# XMICRO-CF_V1_0.net
KiCad netlist of a schematic drawn in EAGLE
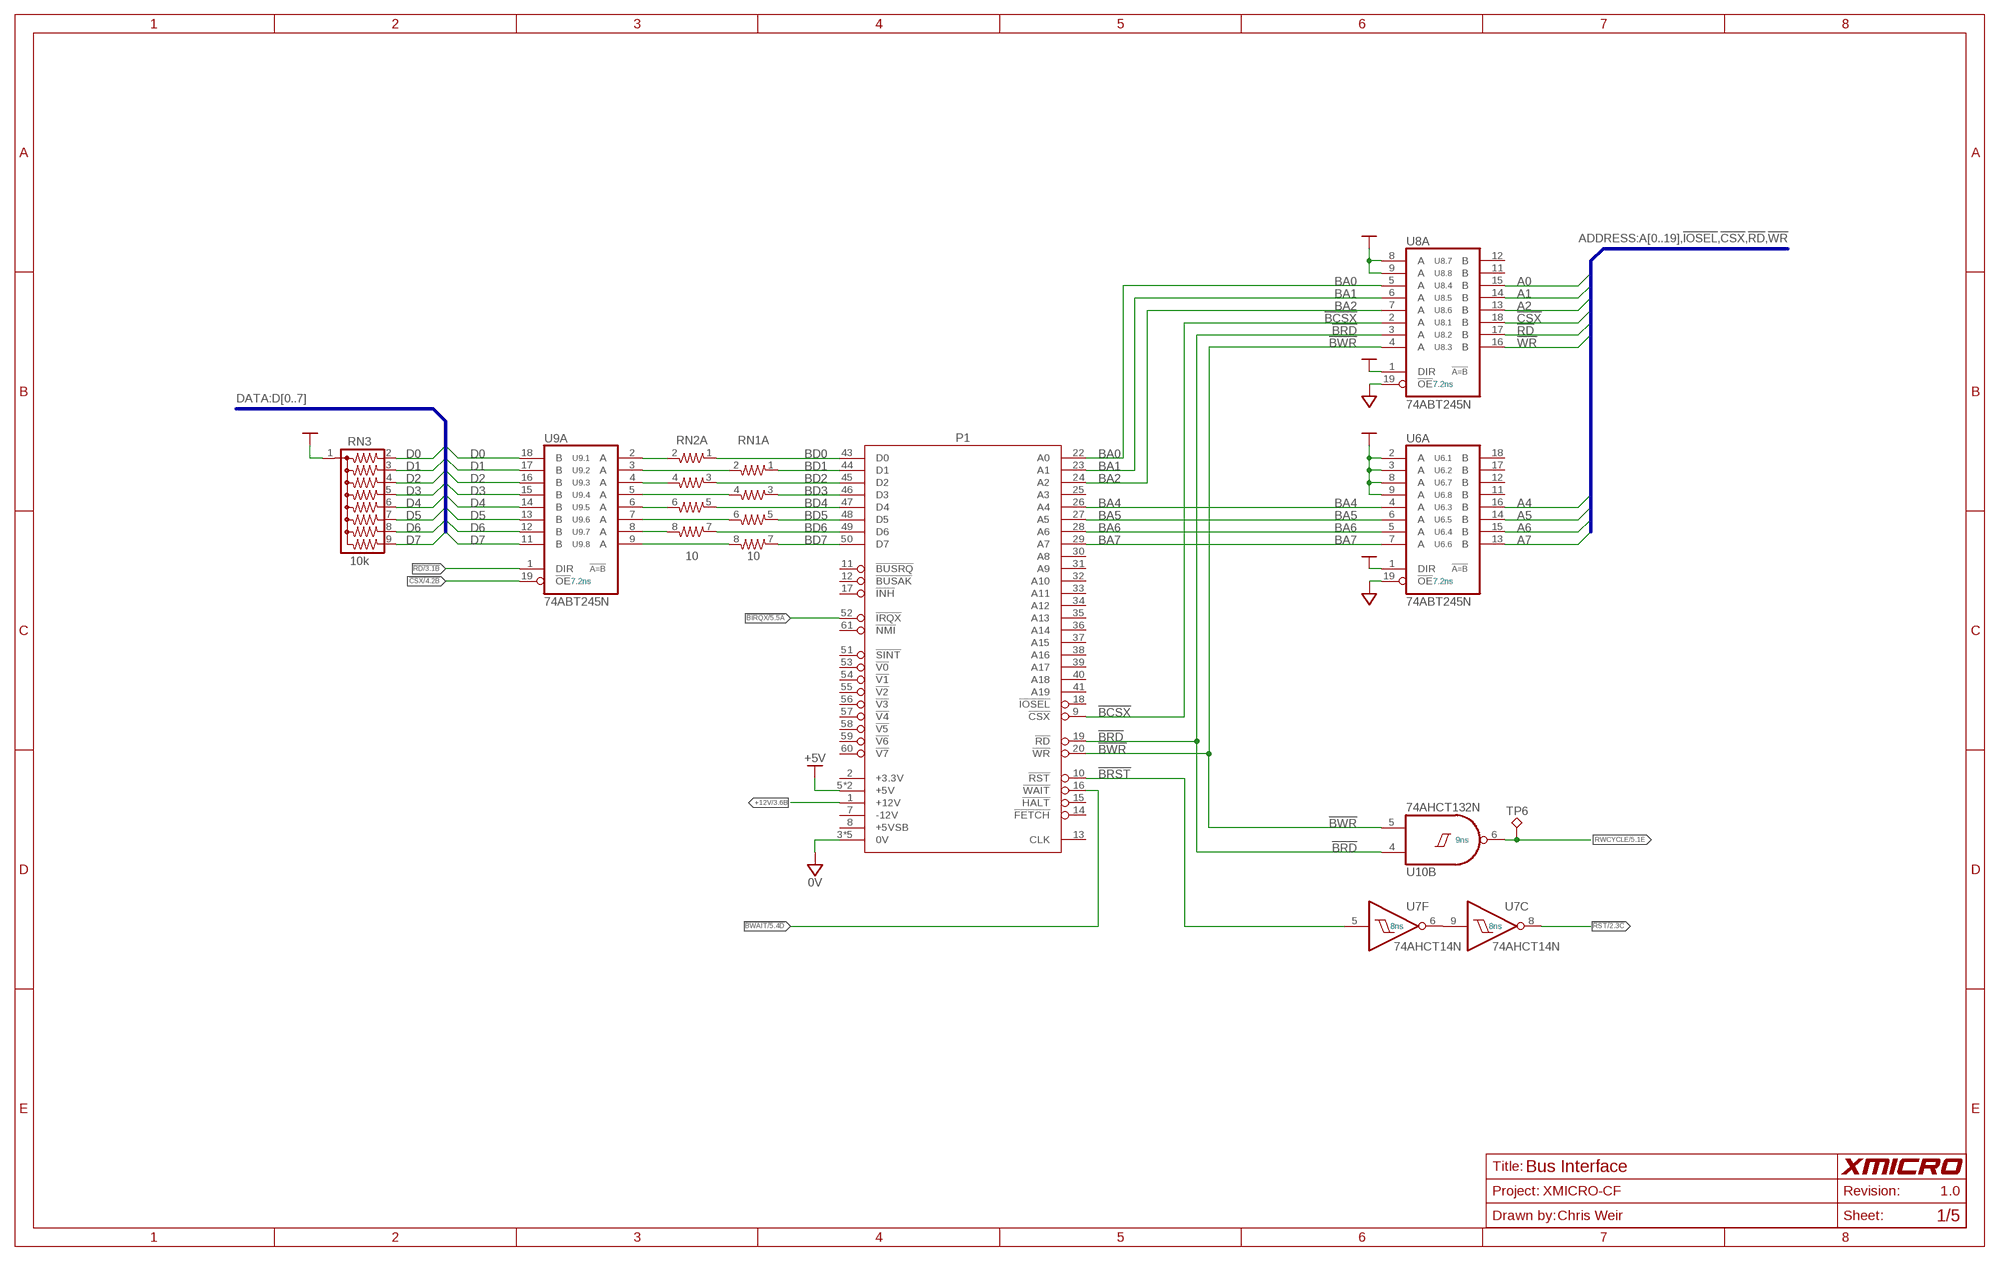
[diagram p0: schematic, sheet 1]
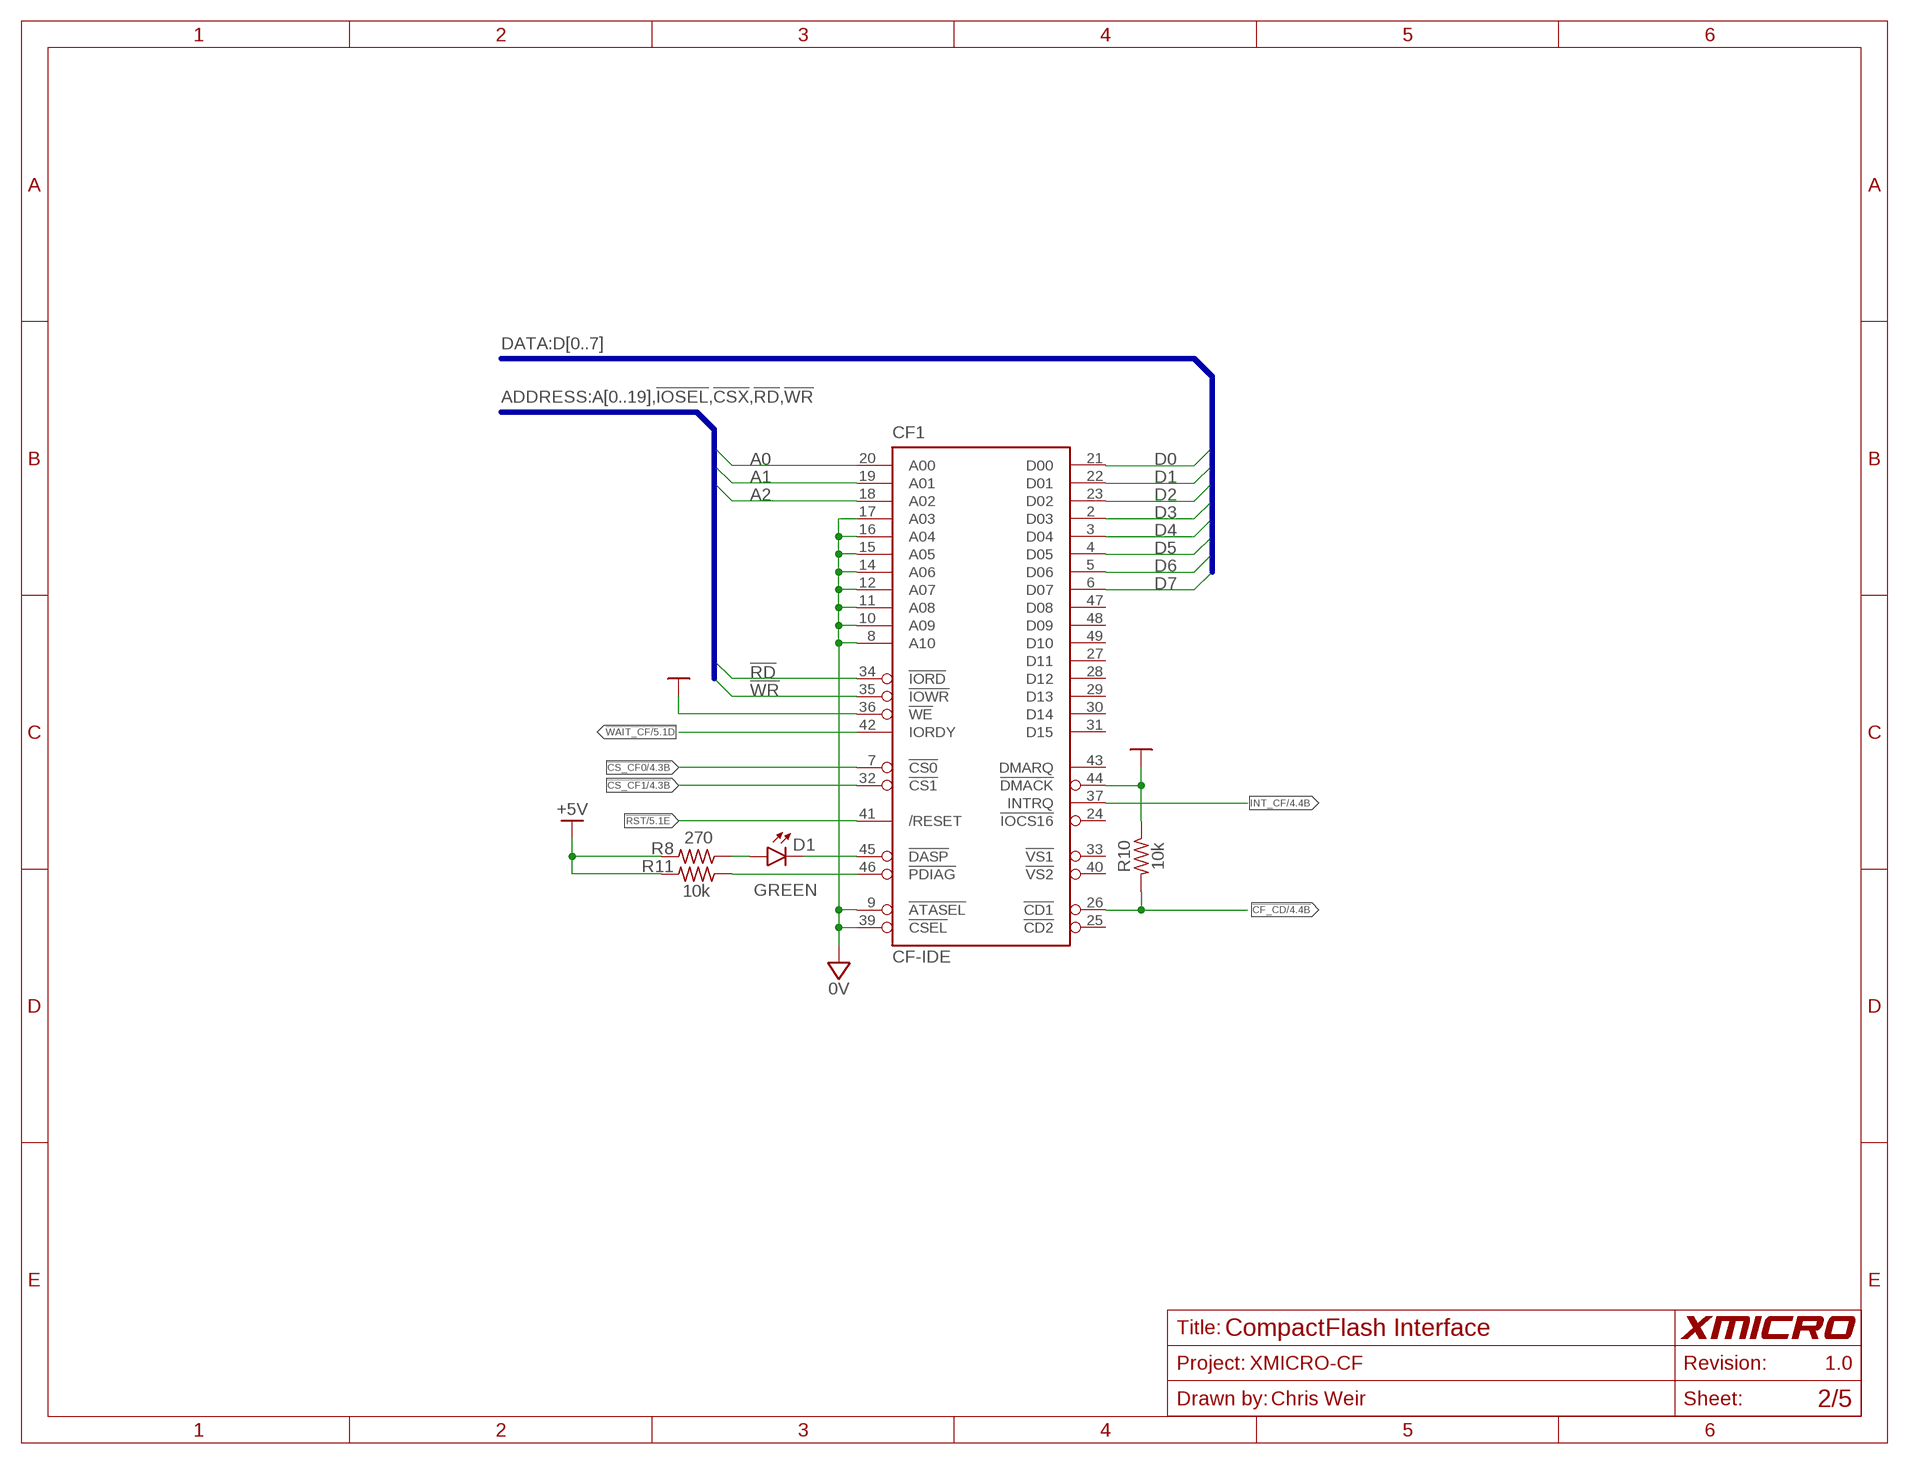
[diagram p1: schematic, sheet 2]
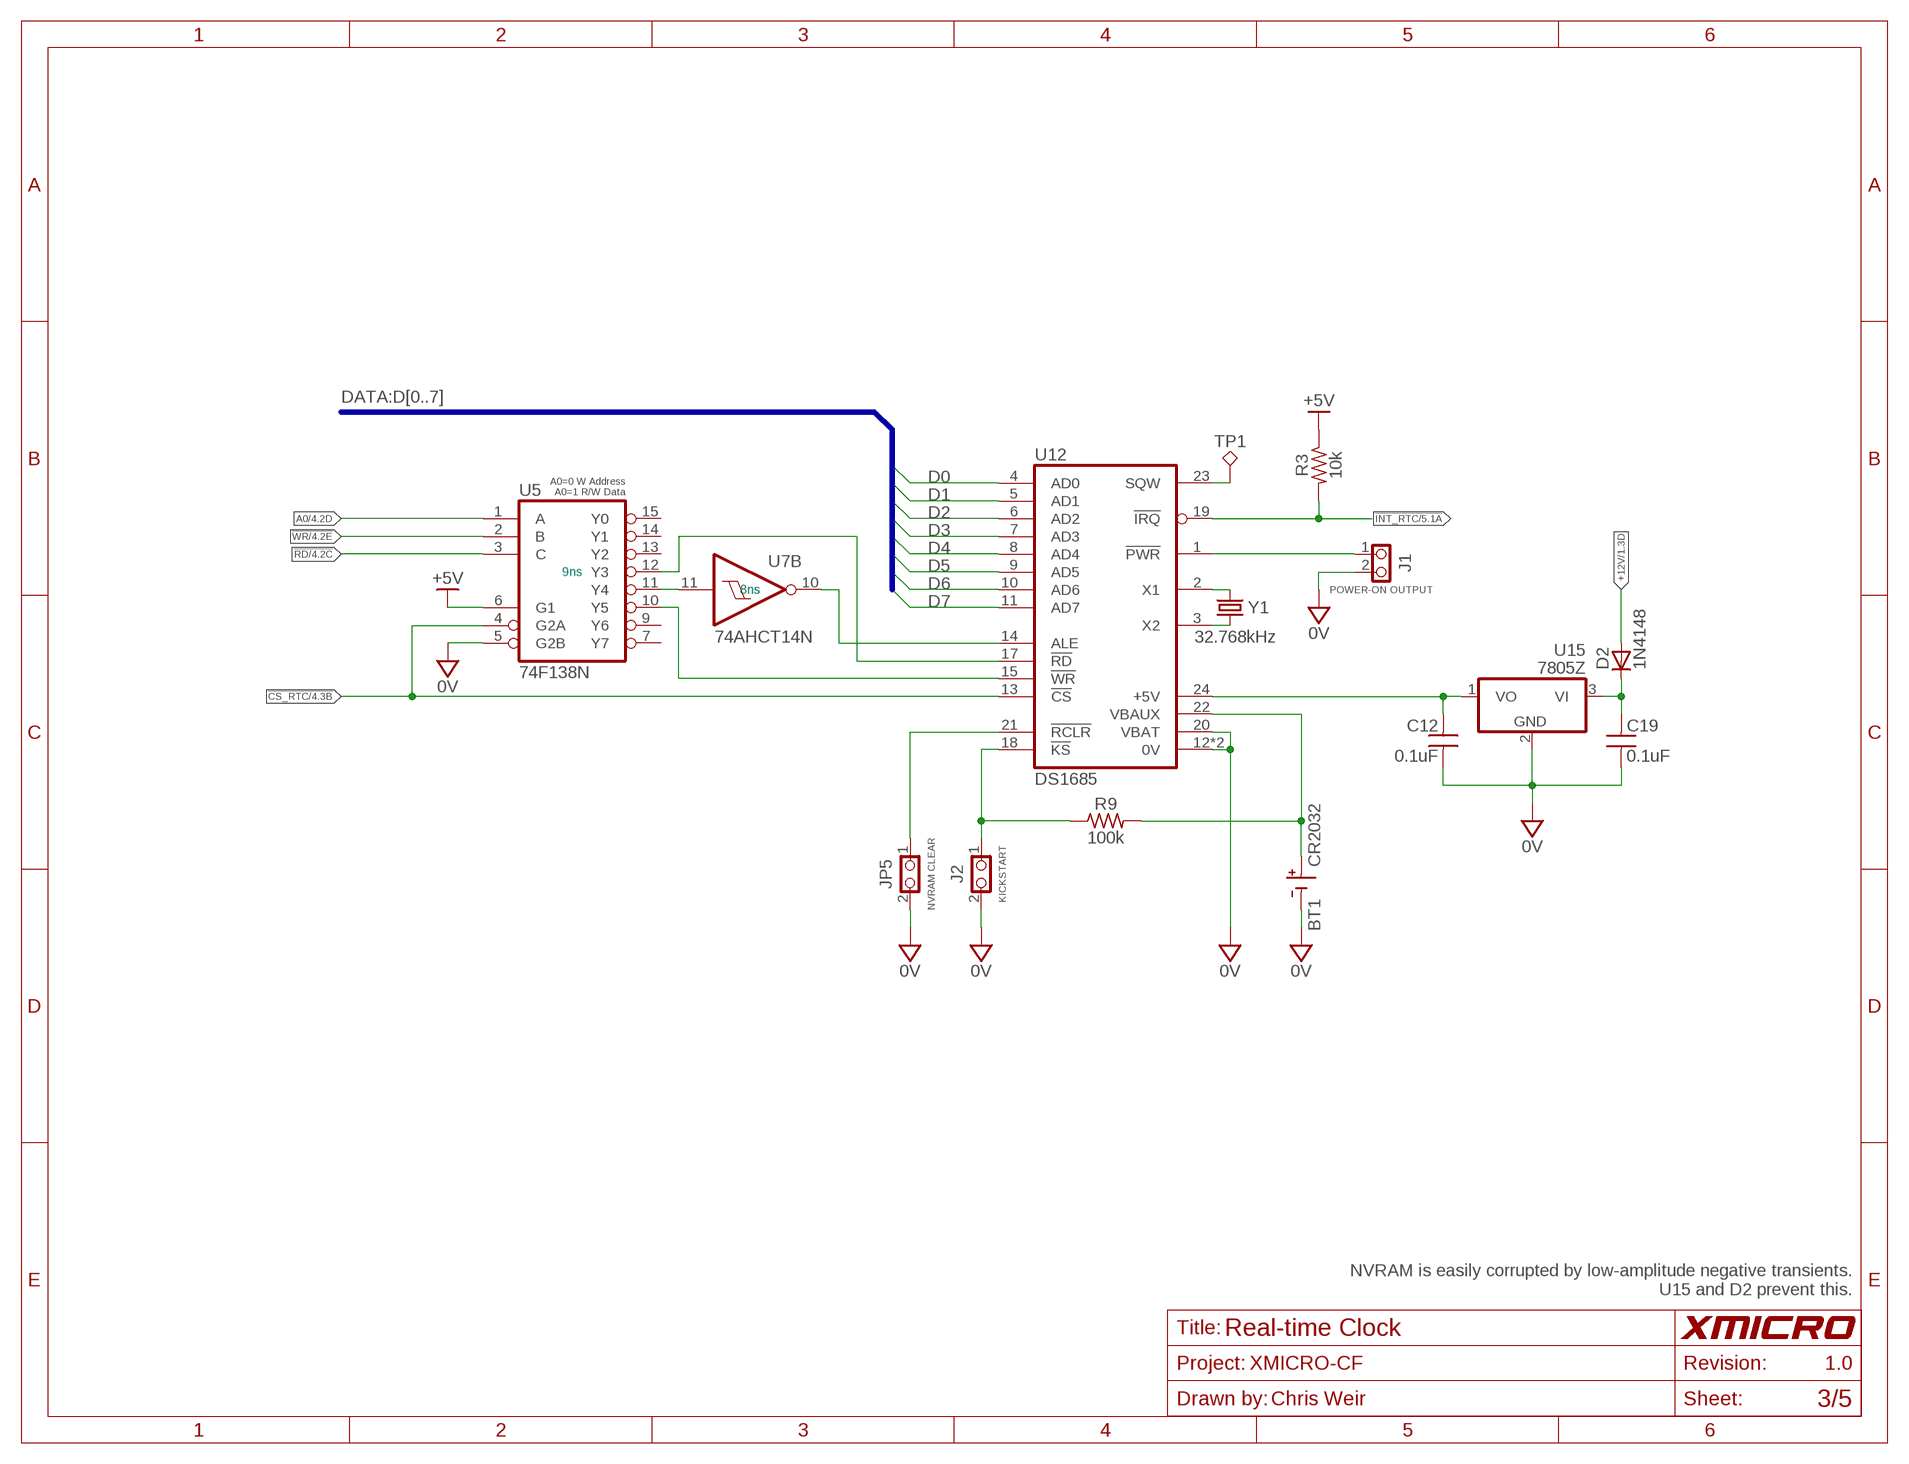
[diagram p2: schematic, sheet 3]
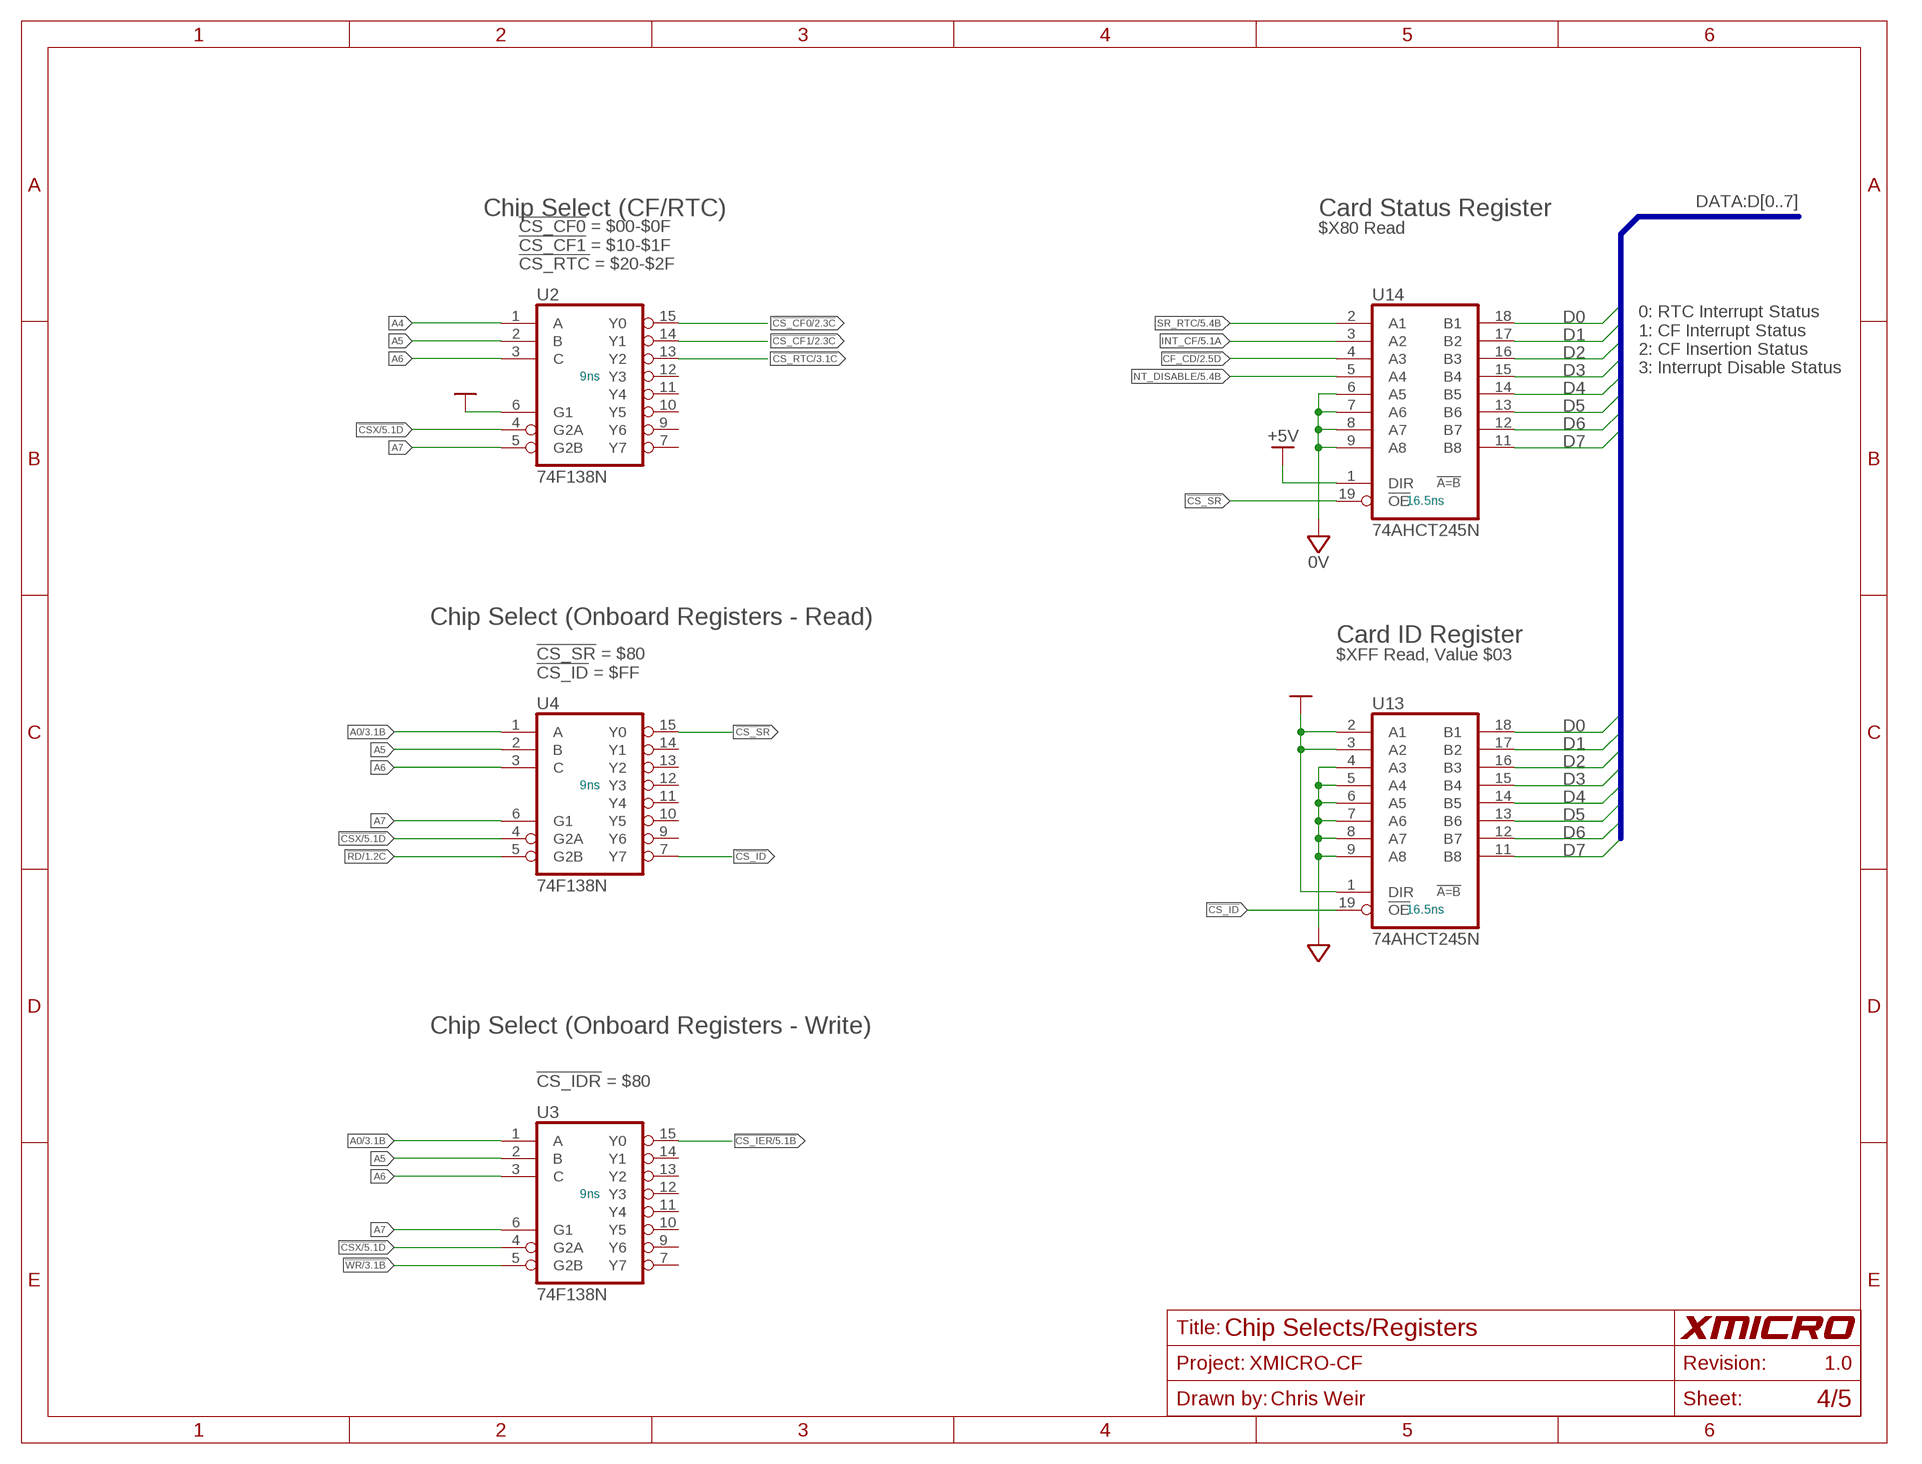
[diagram p3: schematic, sheet 4]
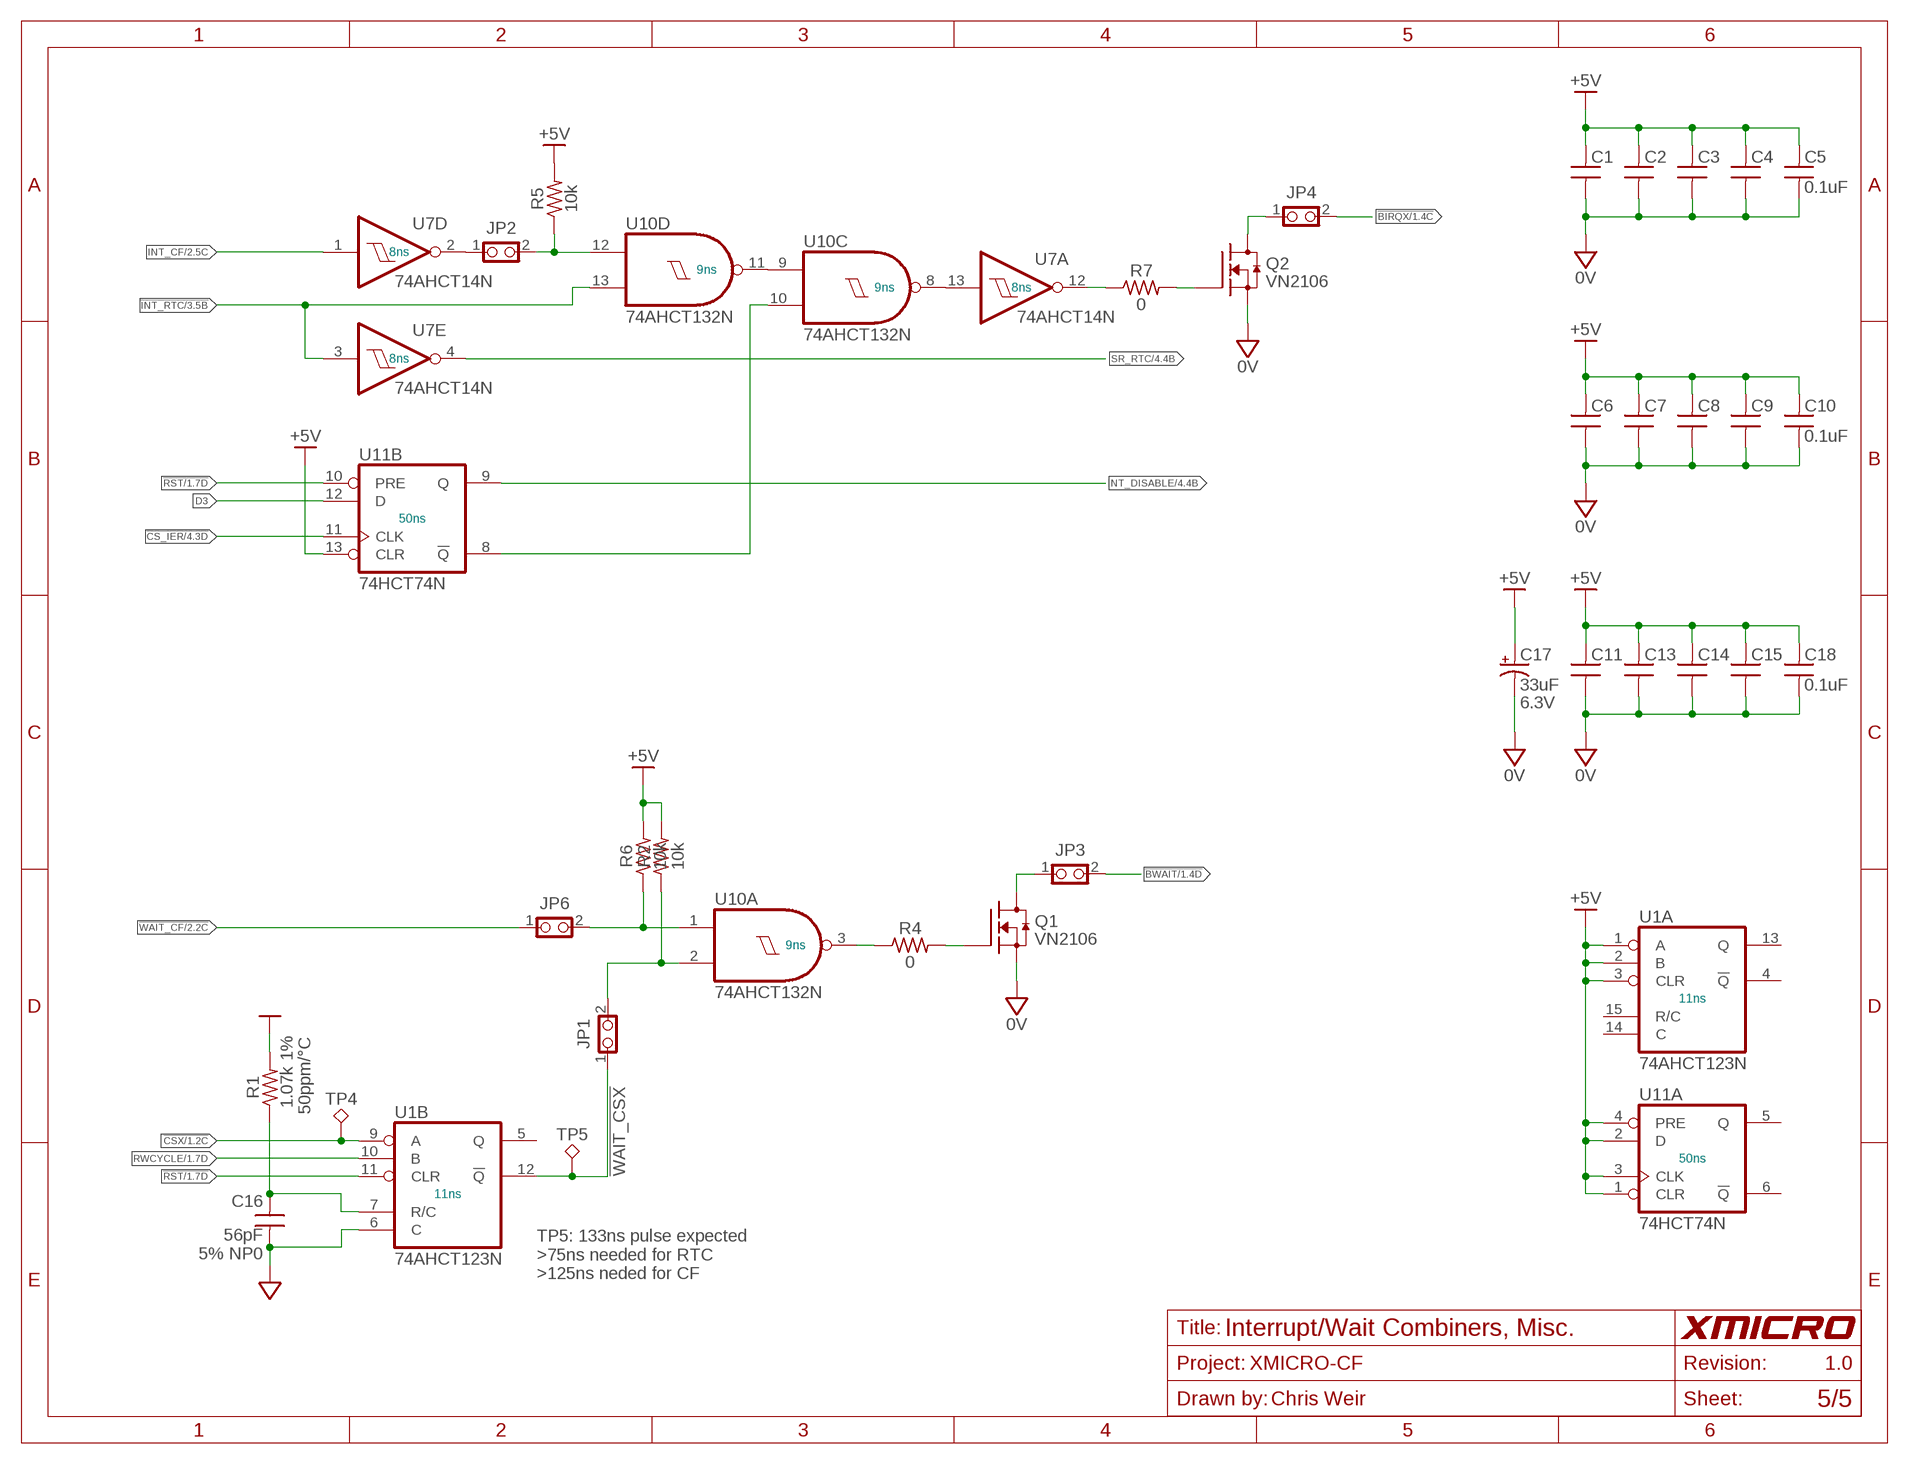
[diagram p4: schematic, sheet 5]

(export (version "E")
  (design (tool "Eeschema 10.0.6"))
  (components
    (comp (ref "C1")
      (value "0.1uF")
      (footprint "eagle-import:C025-024X044")
      (libsource (lib "eagle-import") (part "C-US025-024X044"))
    )
    (comp (ref "C2")
      (value "0.1uF")
      (footprint "eagle-import:C025-024X044")
      (libsource (lib "eagle-import") (part "C-US025-024X044"))
    )
    (comp (ref "C3")
      (value "0.1uF")
      (footprint "eagle-import:C025-024X044")
      (libsource (lib "eagle-import") (part "C-US025-024X044"))
    )
    (comp (ref "C4")
      (value "0.1uF")
      (footprint "eagle-import:C025-024X044")
      (libsource (lib "eagle-import") (part "C-US025-024X044"))
    )
    (comp (ref "C5")
      (value "0.1uF")
      (footprint "eagle-import:C025-024X044")
      (libsource (lib "eagle-import") (part "C-US025-024X044"))
    )
    (comp (ref "C6")
      (value "0.1uF")
      (footprint "eagle-import:C025-024X044")
      (libsource (lib "eagle-import") (part "C-US025-024X044"))
    )
    (comp (ref "C7")
      (value "0.1uF")
      (footprint "eagle-import:C025-024X044")
      (libsource (lib "eagle-import") (part "C-US025-024X044"))
    )
    (comp (ref "C8")
      (value "0.1uF")
      (footprint "eagle-import:C025-024X044")
      (libsource (lib "eagle-import") (part "C-US025-024X044"))
    )
    (comp (ref "C9")
      (value "0.1uF")
      (footprint "eagle-import:C025-024X044")
      (libsource (lib "eagle-import") (part "C-US025-024X044"))
    )
    (comp (ref "C10")
      (value "0.1uF")
      (footprint "eagle-import:C025-024X044")
      (libsource (lib "eagle-import") (part "C-US025-024X044"))
    )
    (comp (ref "C11")
      (value "0.1uF")
      (footprint "eagle-import:C025-024X044")
      (libsource (lib "eagle-import") (part "C-US025-024X044"))
    )
    (comp (ref "C13")
      (value "0.1uF")
      (footprint "eagle-import:C025-024X044")
      (libsource (lib "eagle-import") (part "C-US025-024X044"))
    )
    (comp (ref "C14")
      (value "0.1uF")
      (footprint "eagle-import:C025-024X044")
      (libsource (lib "eagle-import") (part "C-US025-024X044"))
    )
    (comp (ref "C15")
      (value "0.1uF")
      (footprint "eagle-import:C025-024X044")
      (libsource (lib "eagle-import") (part "C-US025-024X044"))
    )
    (comp (ref "C16")
      (value "56pF")
      (footprint "eagle-import:C025-024X044")
      (fields (field (name "TC") "NP0") (field (name "TOLERANCE") "5%"))
      (libsource (lib "eagle-import") (part "C-US025-024X044"))
    )
    (comp (ref "C17")
      (value "33uF")
      (footprint "eagle-import:E2,5-6")
      (fields (field (name "VOLTAGE") "6.3V"))
      (libsource (lib "eagle-import") (part "CPOL-USE2.5-6"))
    )
    (comp (ref "C18")
      (value "0.1uF")
      (footprint "eagle-import:C025-024X044")
      (libsource (lib "eagle-import") (part "C-US025-024X044"))
    )
    (comp (ref "JP1")
      (value "1X2-THRU")
      (footprint "eagle-import:1X2")
      (libsource (lib "eagle-import") (part "1X2-THRU"))
    )
    (comp (ref "JP2")
      (value "1X2-THRU")
      (footprint "eagle-import:1X2")
      (libsource (lib "eagle-import") (part "1X2-THRU"))
    )
    (comp (ref "JP3")
      (value "1X2-THRU")
      (footprint "eagle-import:1X2")
      (libsource (lib "eagle-import") (part "1X2-THRU"))
    )
    (comp (ref "JP4")
      (value "1X2-THRU")
      (footprint "eagle-import:1X2")
      (libsource (lib "eagle-import") (part "1X2-THRU"))
    )
    (comp (ref "JP6")
      (value "1X2-THRU")
      (footprint "eagle-import:1X2")
      (libsource (lib "eagle-import") (part "1X2-THRU"))
    )
    (comp (ref "Q1")
      (value "VN2106")
      (footprint "eagle-import:TO92")
      (libsource (lib "eagle-import") (part "VN2106"))
    )
    (comp (ref "Q2")
      (value "VN2106")
      (footprint "eagle-import:TO92")
      (libsource (lib "eagle-import") (part "VN2106"))
    )
    (comp (ref "R1")
      (value "1.07k")
      (footprint "eagle-import:0207_10")
      (fields (field (name "TC") "50ppm/°C") (field (name "TOLERANCE") "1%"))
      (libsource (lib "eagle-import") (part "R-US_0207/10"))
    )
    (comp (ref "R2")
      (value "10k")
      (footprint "eagle-import:0207_10")
      (libsource (lib "eagle-import") (part "R-US_0207/10"))
    )
    (comp (ref "R4")
      (value "0")
      (footprint "eagle-import:0207_10")
      (libsource (lib "eagle-import") (part "R-US_0207/10"))
    )
    (comp (ref "R5")
      (value "10k")
      (footprint "eagle-import:0207_10")
      (libsource (lib "eagle-import") (part "R-US_0207/10"))
    )
    (comp (ref "R6")
      (value "10k")
      (footprint "eagle-import:0207_10")
      (libsource (lib "eagle-import") (part "R-US_0207/10"))
    )
    (comp (ref "R7")
      (value "0")
      (footprint "eagle-import:0207_12")
      (libsource (lib "eagle-import") (part "R-US_0207/12"))
    )
    (comp (ref "TP4")
      (value "TP-040")
      (footprint "eagle-import:TP-040")
      (libsource (lib "eagle-import") (part "TP-040"))
    )
    (comp (ref "TP5")
      (value "TP-040")
      (footprint "eagle-import:TP-040")
      (libsource (lib "eagle-import") (part "TP-040"))
    )
    (comp (ref "U1")
      (value "74AHCT123N")
      (footprint "eagle-import:DIL16")
      (fields (field (name "TPD") "11ns"))
      (libsource (lib "eagle-import") (part "74123NAHCT"))
    )
    (comp (ref "U7")
      (value "74AHCT14N")
      (footprint "eagle-import:DIL14")
      (fields (field (name "TPD") "8ns") (field (name "TPD_1") "8ns"))
      (libsource (lib "eagle-import") (part "7414NAHCT"))
    )
    (comp (ref "U10")
      (value "74AHCT132N")
      (footprint "eagle-import:DIL14")
      (libsource (lib "eagle-import") (part "74132NAHCT"))
    )
    (comp (ref "U11")
      (value "74HCT74N")
      (footprint "eagle-import:DIL14")
      (libsource (lib "eagle-import") (part "7474NHCT"))
    )
    (comp (ref "P1")
      (value "XMICRO-BUS-EDGE")
      (footprint "eagle-import:EDGE62M")
      (libsource (lib "eagle-import") (part "XMICRO-BUS-EDGE"))
    )
    (comp (ref "RN1")
      (value "10")
      (footprint "eagle-import:SIL8")
      (libsource (lib "eagle-import") (part "E4R"))
    )
    (comp (ref "RN2")
      (value "10")
      (footprint "eagle-import:SIL8")
      (libsource (lib "eagle-import") (part "E4R"))
    )
    (comp (ref "RN3")
      (value "10k")
      (footprint "eagle-import:SIL9")
      (libsource (lib "eagle-import") (part "G08R"))
    )
    (comp (ref "TP6")
      (value "TP-040")
      (footprint "eagle-import:TP-040")
      (libsource (lib "eagle-import") (part "TP-040"))
    )
    (comp (ref "U6")
      (value "74ABT245N")
      (footprint "eagle-import:DIL20")
      (fields (field (name "TPD") "7.2ns"))
      (libsource (lib "eagle-import") (part "74245-SNABT"))
    )
    (comp (ref "U8")
      (value "74ABT245N")
      (footprint "eagle-import:DIL20")
      (libsource (lib "eagle-import") (part "74245-SNABT"))
    )
    (comp (ref "U9")
      (value "74ABT245N")
      (footprint "eagle-import:DIL20")
      (fields (field (name "TPD") "7.2ns"))
      (libsource (lib "eagle-import") (part "74245-SNABT"))
    )
    (comp (ref "CF1")
      (value "CF-IDE")
      (footprint "eagle-import:CF-KYOCERA")
      (libsource (lib "eagle-import") (part "CF-IDE"))
    )
    (comp (ref "D1")
      (value "GREEN")
      (footprint "eagle-import:LED-3R")
      (libsource (lib "eagle-import") (part "LED3MM-R"))
    )
    (comp (ref "R8")
      (value "270")
      (footprint "eagle-import:0207_10")
      (libsource (lib "eagle-import") (part "R-US_0207/10"))
    )
    (comp (ref "R10")
      (value "10k")
      (footprint "eagle-import:0207_10")
      (libsource (lib "eagle-import") (part "R-US_0207/10"))
    )
    (comp (ref "R11")
      (value "10k")
      (footprint "eagle-import:0207_10")
      (libsource (lib "eagle-import") (part "R-US_0207/10"))
    )
    (comp (ref "U2")
      (value "74F138N")
      (footprint "eagle-import:DIL16")
      (libsource (lib "eagle-import") (part "74138NF"))
    )
    (comp (ref "U3")
      (value "74F138N")
      (footprint "eagle-import:DIL16")
      (libsource (lib "eagle-import") (part "74138NF"))
    )
    (comp (ref "U4")
      (value "74F138N")
      (footprint "eagle-import:DIL16")
      (libsource (lib "eagle-import") (part "74138NF"))
    )
    (comp (ref "U13")
      (value "74AHCT245N")
      (footprint "eagle-import:DIL20")
      (libsource (lib "eagle-import") (part "74245NAHCT"))
    )
    (comp (ref "U14")
      (value "74AHCT245N")
      (footprint "eagle-import:DIL20")
      (libsource (lib "eagle-import") (part "74245NAHCT"))
    )
    (comp (ref "BT1")
      (value "CR2032")
      (footprint "eagle-import:BU2032")
      (libsource (lib "eagle-import") (part "CR2032TH"))
    )
    (comp (ref "C12")
      (value "0.1uF")
      (footprint "eagle-import:C025-024X044")
      (libsource (lib "eagle-import") (part "C-US025-024X044"))
    )
    (comp (ref "C19")
      (value "0.1uF")
      (footprint "eagle-import:C025-024X044")
      (libsource (lib "eagle-import") (part "C-US025-024X044"))
    )
    (comp (ref "D2")
      (value "1N4148")
      (footprint "eagle-import:DO35-7")
      (libsource (lib "eagle-import") (part "1N4148DO35-7"))
    )
    (comp (ref "J1")
      (value "1X2")
      (footprint "eagle-import:1X2")
      (libsource (lib "eagle-import") (part "1X2"))
    )
    (comp (ref "J2")
      (value "1X2-THRU")
      (footprint "eagle-import:1X2")
      (libsource (lib "eagle-import") (part "1X2-THRU"))
    )
    (comp (ref "JP5")
      (value "1X2-THRU")
      (footprint "eagle-import:1X2")
      (libsource (lib "eagle-import") (part "1X2-THRU"))
    )
    (comp (ref "R3")
      (value "10k")
      (footprint "eagle-import:0207_10")
      (libsource (lib "eagle-import") (part "R-US_0207/10"))
    )
    (comp (ref "R9")
      (value "100k")
      (footprint "eagle-import:0207_10")
      (libsource (lib "eagle-import") (part "R-US_0207/10"))
    )
    (comp (ref "TP1")
      (value "TP-040")
      (footprint "eagle-import:TP-040")
      (libsource (lib "eagle-import") (part "TP-040"))
    )
    (comp (ref "U5")
      (value "74F138N")
      (footprint "eagle-import:DIL16")
      (libsource (lib "eagle-import") (part "74138NF"))
    )
    (comp (ref "U12")
      (value "DS1685")
      (footprint "eagle-import:DIL24")
      (libsource (lib "eagle-import") (part "DS1685"))
    )
    (comp (ref "U15")
      (value "7805Z")
      (footprint "eagle-import:TO92")
      (libsource (lib "eagle-import") (part "78Z05"))
    )
    (comp (ref "Y1")
      (value "32.768kHz")
      (footprint "eagle-import:CRYSTAL-3X8N")
      (libsource (lib "eagle-import") (part "CRYSTAL-3X8"))
    )
  )
  (nets
    (net (code "36") (name "+5V") (class "Default")
      (node (ref "C1") (pin "1") (pinfunction "1_1") (pintype "passive"))
      (node (ref "C10") (pin "1") (pinfunction "1_1") (pintype "passive"))
      (node (ref "C11") (pin "1") (pinfunction "1_1") (pintype "passive"))
      (node (ref "C13") (pin "1") (pinfunction "1_1") (pintype "passive"))
      (node (ref "C14") (pin "1") (pinfunction "1_1") (pintype "passive"))
      (node (ref "C15") (pin "1") (pinfunction "1_1") (pintype "passive"))
      (node (ref "C17") (pin "+") (pinfunction "+_+") (pintype "passive"))
      (node (ref "C18") (pin "1") (pinfunction "1_1") (pintype "passive"))
      (node (ref "C2") (pin "1") (pinfunction "1_1") (pintype "passive"))
      (node (ref "C3") (pin "1") (pinfunction "1_1") (pintype "passive"))
      (node (ref "C4") (pin "1") (pinfunction "1_1") (pintype "passive"))
      (node (ref "C5") (pin "1") (pinfunction "1_1") (pintype "passive"))
      (node (ref "C6") (pin "1") (pinfunction "1_1") (pintype "passive"))
      (node (ref "C7") (pin "1") (pinfunction "1_1") (pintype "passive"))
      (node (ref "C8") (pin "1") (pinfunction "1_1") (pintype "passive"))
      (node (ref "C9") (pin "1") (pinfunction "1_1") (pintype "passive"))
      (node (ref "CF1") (pin "36") (pinfunction "~{WE}_36") (pintype "input"))
      (node (ref "CF1") (pin "44") (pinfunction "~{DMACK}_44") (pintype "input"))
      (node (ref "P1") (pin "5") (pinfunction "+5V_5") (pintype "bidirectional"))
      (node (ref "P1") (pin "6") (pinfunction "+5V_6") (pintype "bidirectional"))
      (node (ref "R1") (pin "2") (pinfunction "2_2") (pintype "passive"))
      (node (ref "R10") (pin "1") (pinfunction "1_1") (pintype "passive"))
      (node (ref "R11") (pin "2") (pinfunction "2_2") (pintype "passive"))
      (node (ref "R2") (pin "2") (pinfunction "2_2") (pintype "passive"))
      (node (ref "R3") (pin "1") (pinfunction "1_1") (pintype "passive"))
      (node (ref "R5") (pin "2") (pinfunction "2_2") (pintype "passive"))
      (node (ref "R6") (pin "2") (pinfunction "2_2") (pintype "passive"))
      (node (ref "R8") (pin "2") (pinfunction "2_2") (pintype "passive"))
      (node (ref "RN3") (pin "1") (pinfunction "1_1") (pintype "passive"))
      (node (ref "U1") (pin "1") (pinfunction "A_1") (pintype "input"))
      (node (ref "U1") (pin "2") (pinfunction "B_2") (pintype "input"))
      (node (ref "U1") (pin "3") (pinfunction "CLR_3") (pintype "input"))
      (node (ref "U11") (pin "1") (pinfunction "CLR_1") (pintype "input"))
      (node (ref "U11") (pin "13") (pinfunction "CLR_13") (pintype "input"))
      (node (ref "U11") (pin "2") (pinfunction "D_2") (pintype "input"))
      (node (ref "U11") (pin "3") (pinfunction "CLK_3") (pintype "input"))
      (node (ref "U11") (pin "4") (pinfunction "PRE_4") (pintype "input"))
      (node (ref "U13") (pin "1") (pinfunction "DIR_1") (pintype "input"))
      (node (ref "U13") (pin "2") (pinfunction "A1_2") (pintype "bidirectional"))
      (node (ref "U13") (pin "3") (pinfunction "A2_3") (pintype "bidirectional"))
      (node (ref "U14") (pin "1") (pinfunction "DIR_1") (pintype "input"))
      (node (ref "U2") (pin "6") (pinfunction "G1_6") (pintype "input"))
      (node (ref "U5") (pin "6") (pinfunction "G1_6") (pintype "input"))
      (node (ref "U6") (pin "1") (pinfunction "DIR_1") (pintype "input"))
      (node (ref "U6") (pin "2") (pinfunction "A_2") (pintype "bidirectional"))
      (node (ref "U6") (pin "3") (pinfunction "A_3") (pintype "bidirectional"))
      (node (ref "U6") (pin "8") (pinfunction "A_8") (pintype "bidirectional"))
      (node (ref "U6") (pin "9") (pinfunction "A_9") (pintype "bidirectional"))
      (node (ref "U8") (pin "1") (pinfunction "DIR_1") (pintype "input"))
      (node (ref "U8") (pin "8") (pinfunction "A_8") (pintype "bidirectional"))
      (node (ref "U8") (pin "9") (pinfunction "A_9") (pintype "bidirectional"))
    )
    (net (code "37") (name "+12V") (class "Default")
      (node (ref "D2") (pin "A") (pinfunction "A_A") (pintype "passive"))
      (node (ref "P1") (pin "1") (pinfunction "+12V_1") (pintype "bidirectional"))
    )
    (net (code "44") (name "0V") (class "Default")
      (node (ref "BT1") (pin "N") (pinfunction "-_N") (pintype "passive"))
      (node (ref "C1") (pin "2") (pinfunction "2_2") (pintype "passive"))
      (node (ref "C10") (pin "2") (pinfunction "2_2") (pintype "passive"))
      (node (ref "C11") (pin "2") (pinfunction "2_2") (pintype "passive"))
      (node (ref "C12") (pin "2") (pinfunction "2_2") (pintype "passive"))
      (node (ref "C13") (pin "2") (pinfunction "2_2") (pintype "passive"))
      (node (ref "C14") (pin "2") (pinfunction "2_2") (pintype "passive"))
      (node (ref "C15") (pin "2") (pinfunction "2_2") (pintype "passive"))
      (node (ref "C16") (pin "2") (pinfunction "2_2") (pintype "passive"))
      (node (ref "C17") (pin "-") (pinfunction "-_-") (pintype "passive"))
      (node (ref "C18") (pin "2") (pinfunction "2_2") (pintype "passive"))
      (node (ref "C19") (pin "2") (pinfunction "2_2") (pintype "passive"))
      (node (ref "C2") (pin "2") (pinfunction "2_2") (pintype "passive"))
      (node (ref "C3") (pin "2") (pinfunction "2_2") (pintype "passive"))
      (node (ref "C4") (pin "2") (pinfunction "2_2") (pintype "passive"))
      (node (ref "C5") (pin "2") (pinfunction "2_2") (pintype "passive"))
      (node (ref "C6") (pin "2") (pinfunction "2_2") (pintype "passive"))
      (node (ref "C7") (pin "2") (pinfunction "2_2") (pintype "passive"))
      (node (ref "C8") (pin "2") (pinfunction "2_2") (pintype "passive"))
      (node (ref "C9") (pin "2") (pinfunction "2_2") (pintype "passive"))
      (node (ref "CF1") (pin "10") (pinfunction "A09_10") (pintype "input"))
      (node (ref "CF1") (pin "11") (pinfunction "A08_11") (pintype "input"))
      (node (ref "CF1") (pin "12") (pinfunction "A07_12") (pintype "input"))
      (node (ref "CF1") (pin "14") (pinfunction "A06_14") (pintype "input"))
      (node (ref "CF1") (pin "15") (pinfunction "A05_15") (pintype "input"))
      (node (ref "CF1") (pin "16") (pinfunction "A04_16") (pintype "input"))
      (node (ref "CF1") (pin "17") (pinfunction "A03_17") (pintype "input"))
      (node (ref "CF1") (pin "39") (pinfunction "~{CSEL}_39") (pintype "input"))
      (node (ref "CF1") (pin "8") (pinfunction "A10_8") (pintype "input"))
      (node (ref "CF1") (pin "9") (pinfunction "~{ATASEL}_9") (pintype "input"))
      (node (ref "J1") (pin "2") (pinfunction "2_2") (pintype "passive"))
      (node (ref "J2") (pin "2") (pinfunction "2_2") (pintype "passive"))
      (node (ref "JP5") (pin "2") (pinfunction "2_2") (pintype "passive"))
      (node (ref "P1") (pin "21") (pinfunction "0V_21") (pintype "bidirectional"))
      (node (ref "P1") (pin "3") (pinfunction "0V_3") (pintype "bidirectional"))
      (node (ref "P1") (pin "4") (pinfunction "0V_4") (pintype "bidirectional"))
      (node (ref "P1") (pin "42") (pinfunction "0V_42") (pintype "bidirectional"))
      (node (ref "P1") (pin "62") (pinfunction "0V_62") (pintype "bidirectional"))
      (node (ref "Q1") (pin "1") (pinfunction "S_1") (pintype "passive"))
      (node (ref "Q2") (pin "1") (pinfunction "S_1") (pintype "passive"))
      (node (ref "U1") (pin "6") (pinfunction "C_6") (pintype "input"))
      (node (ref "U12") (pin "12") (pinfunction "0V_12") (pintype "input"))
      (node (ref "U12") (pin "16") (pinfunction "0V_16") (pintype "input"))
      (node (ref "U12") (pin "20") (pinfunction "VBAT_20") (pintype "input"))
      (node (ref "U13") (pin "4") (pinfunction "A3_4") (pintype "bidirectional"))
      (node (ref "U13") (pin "5") (pinfunction "A4_5") (pintype "bidirectional"))
      (node (ref "U13") (pin "6") (pinfunction "A5_6") (pintype "bidirectional"))
      (node (ref "U13") (pin "7") (pinfunction "A6_7") (pintype "bidirectional"))
      (node (ref "U13") (pin "8") (pinfunction "A7_8") (pintype "bidirectional"))
      (node (ref "U13") (pin "9") (pinfunction "A8_9") (pintype "bidirectional"))
      (node (ref "U14") (pin "6") (pinfunction "A5_6") (pintype "bidirectional"))
      (node (ref "U14") (pin "7") (pinfunction "A6_7") (pintype "bidirectional"))
      (node (ref "U14") (pin "8") (pinfunction "A7_8") (pintype "bidirectional"))
      (node (ref "U14") (pin "9") (pinfunction "A8_9") (pintype "bidirectional"))
      (node (ref "U15") (pin "2") (pinfunction "0V_2") (pintype "passive"))
      (node (ref "U5") (pin "5") (pinfunction "G2B_5") (pintype "input"))
      (node (ref "U6") (pin "19") (pinfunction "~{OE}_19") (pintype "input"))
      (node (ref "U8") (pin "19") (pinfunction "~{OE}_19") (pintype "input"))
    )
    (net (code "45") (name "A0") (class "Default")
      (node (ref "CF1") (pin "20") (pinfunction "A00_20") (pintype "input"))
      (node (ref "U3") (pin "1") (pinfunction "A_1") (pintype "input"))
      (node (ref "U4") (pin "1") (pinfunction "A_1") (pintype "input"))
      (node (ref "U5") (pin "1") (pinfunction "A_1") (pintype "input"))
      (node (ref "U8") (pin "15") (pinfunction "B_15") (pintype "bidirectional"))
    )
    (net (code "46") (name "A1") (class "Default")
      (node (ref "CF1") (pin "19") (pinfunction "A01_19") (pintype "input"))
      (node (ref "U8") (pin "14") (pinfunction "B_14") (pintype "bidirectional"))
    )
    (net (code "47") (name "A2") (class "Default")
      (node (ref "CF1") (pin "18") (pinfunction "A02_18") (pintype "input"))
      (node (ref "U8") (pin "13") (pinfunction "B_13") (pintype "bidirectional"))
    )
    (net (code "48") (name "A4") (class "Default")
      (node (ref "U2") (pin "1") (pinfunction "A_1") (pintype "input"))
      (node (ref "U6") (pin "16") (pinfunction "B_16") (pintype "bidirectional"))
    )
    (net (code "49") (name "A5") (class "Default")
      (node (ref "U2") (pin "2") (pinfunction "B_2") (pintype "input"))
      (node (ref "U3") (pin "2") (pinfunction "B_2") (pintype "input"))
      (node (ref "U4") (pin "2") (pinfunction "B_2") (pintype "input"))
      (node (ref "U6") (pin "14") (pinfunction "B_14") (pintype "bidirectional"))
    )
    (net (code "50") (name "A6") (class "Default")
      (node (ref "U2") (pin "3") (pinfunction "C_3") (pintype "input"))
      (node (ref "U3") (pin "3") (pinfunction "C_3") (pintype "input"))
      (node (ref "U4") (pin "3") (pinfunction "C_3") (pintype "input"))
      (node (ref "U6") (pin "15") (pinfunction "B_15") (pintype "bidirectional"))
    )
    (net (code "51") (name "A7") (class "Default")
      (node (ref "U2") (pin "5") (pinfunction "G2B_5") (pintype "input"))
      (node (ref "U3") (pin "6") (pinfunction "G1_6") (pintype "input"))
      (node (ref "U4") (pin "6") (pinfunction "G1_6") (pintype "input"))
      (node (ref "U6") (pin "13") (pinfunction "B_13") (pintype "bidirectional"))
    )
    (net (code "52") (name "BA0") (class "Default")
      (node (ref "P1") (pin "22") (pinfunction "A0_22") (pintype "bidirectional"))
      (node (ref "U8") (pin "5") (pinfunction "A_5") (pintype "bidirectional"))
    )
    (net (code "53") (name "BA1") (class "Default")
      (node (ref "P1") (pin "23") (pinfunction "A1_23") (pintype "bidirectional"))
      (node (ref "U8") (pin "6") (pinfunction "A_6") (pintype "bidirectional"))
    )
    (net (code "54") (name "BA2") (class "Default")
      (node (ref "P1") (pin "24") (pinfunction "A2_24") (pintype "bidirectional"))
      (node (ref "U8") (pin "7") (pinfunction "A_7") (pintype "bidirectional"))
    )
    (net (code "55") (name "BA4") (class "Default")
      (node (ref "P1") (pin "26") (pinfunction "A4_26") (pintype "bidirectional"))
      (node (ref "U6") (pin "4") (pinfunction "A_4") (pintype "bidirectional"))
    )
    (net (code "56") (name "BA5") (class "Default")
      (node (ref "P1") (pin "27") (pinfunction "A5_27") (pintype "bidirectional"))
      (node (ref "U6") (pin "6") (pinfunction "A_6") (pintype "bidirectional"))
    )
    (net (code "57") (name "BA6") (class "Default")
      (node (ref "P1") (pin "28") (pinfunction "A6_28") (pintype "bidirectional"))
      (node (ref "U6") (pin "5") (pinfunction "A_5") (pintype "bidirectional"))
    )
    (net (code "58") (name "BA7") (class "Default")
      (node (ref "P1") (pin "29") (pinfunction "A7_29") (pintype "bidirectional"))
      (node (ref "U6") (pin "7") (pinfunction "A_7") (pintype "bidirectional"))
    )
    (net (code "59") (name "BD0") (class "Default")
      (node (ref "P1") (pin "43") (pinfunction "D0_43") (pintype "bidirectional"))
      (node (ref "RN2") (pin "1") (pinfunction "1_1") (pintype "passive"))
    )
    (net (code "60") (name "BD1") (class "Default")
      (node (ref "P1") (pin "44") (pinfunction "D1_44") (pintype "bidirectional"))
      (node (ref "RN1") (pin "1") (pinfunction "1_1") (pintype "passive"))
    )
    (net (code "61") (name "BD2") (class "Default")
      (node (ref "P1") (pin "45") (pinfunction "D2_45") (pintype "bidirectional"))
      (node (ref "RN2") (pin "3") (pinfunction "1_3") (pintype "passive"))
    )
    (net (code "62") (name "BD3") (class "Default")
      (node (ref "P1") (pin "46") (pinfunction "D3_46") (pintype "bidirectional"))
      (node (ref "RN1") (pin "3") (pinfunction "1_3") (pintype "passive"))
    )
    (net (code "63") (name "BD4") (class "Default")
      (node (ref "P1") (pin "47") (pinfunction "D4_47") (pintype "bidirectional"))
      (node (ref "RN2") (pin "5") (pinfunction "1_5") (pintype "passive"))
    )
    (net (code "64") (name "BD5") (class "Default")
      (node (ref "P1") (pin "48") (pinfunction "D5_48") (pintype "bidirectional"))
      (node (ref "RN1") (pin "5") (pinfunction "1_5") (pintype "passive"))
    )
    (net (code "65") (name "BD6") (class "Default")
      (node (ref "P1") (pin "49") (pinfunction "D6_49") (pintype "bidirectional"))
      (node (ref "RN2") (pin "7") (pinfunction "1_7") (pintype "passive"))
    )
    (net (code "66") (name "BD7") (class "Default")
      (node (ref "P1") (pin "50") (pinfunction "D7_50") (pintype "bidirectional"))
      (node (ref "RN1") (pin "7") (pinfunction "1_7") (pintype "passive"))
    )
    (net (code "67") (name "D0") (class "Default")
      (node (ref "CF1") (pin "21") (pinfunction "D00_21") (pintype "tri_state"))
      (node (ref "RN3") (pin "2") (pinfunction "2_2") (pintype "passive"))
      (node (ref "U12") (pin "4") (pinfunction "AD0_4") (pintype "tri_state"))
      (node (ref "U13") (pin "18") (pinfunction "B1_18") (pintype "bidirectional"))
      (node (ref "U14") (pin "18") (pinfunction "B1_18") (pintype "bidirectional"))
      (node (ref "U9") (pin "18") (pinfunction "B_18") (pintype "bidirectional"))
    )
    (net (code "68") (name "D1") (class "Default")
      (node (ref "CF1") (pin "22") (pinfunction "D01_22") (pintype "tri_state"))
      (node (ref "RN3") (pin "3") (pinfunction "3_3") (pintype "passive"))
      (node (ref "U12") (pin "5") (pinfunction "AD1_5") (pintype "tri_state"))
      (node (ref "U13") (pin "17") (pinfunction "B2_17") (pintype "bidirectional"))
      (node (ref "U14") (pin "17") (pinfunction "B2_17") (pintype "bidirectional"))
      (node (ref "U9") (pin "17") (pinfunction "B_17") (pintype "bidirectional"))
    )
    (net (code "69") (name "D2") (class "Default")
      (node (ref "CF1") (pin "23") (pinfunction "D02_23") (pintype "tri_state"))
      (node (ref "RN3") (pin "4") (pinfunction "4_4") (pintype "passive"))
      (node (ref "U12") (pin "6") (pinfunction "AD2_6") (pintype "tri_state"))
      (node (ref "U13") (pin "16") (pinfunction "B3_16") (pintype "bidirectional"))
      (node (ref "U14") (pin "16") (pinfunction "B3_16") (pintype "bidirectional"))
      (node (ref "U9") (pin "16") (pinfunction "B_16") (pintype "bidirectional"))
    )
    (net (code "70") (name "D3") (class "Default")
      (node (ref "CF1") (pin "2") (pinfunction "D03_2") (pintype "tri_state"))
      (node (ref "RN3") (pin "5") (pinfunction "5_5") (pintype "passive"))
      (node (ref "U11") (pin "12") (pinfunction "D_12") (pintype "input"))
      (node (ref "U12") (pin "7") (pinfunction "AD3_7") (pintype "tri_state"))
      (node (ref "U13") (pin "15") (pinfunction "B4_15") (pintype "bidirectional"))
      (node (ref "U14") (pin "15") (pinfunction "B4_15") (pintype "bidirectional"))
      (node (ref "U9") (pin "15") (pinfunction "B_15") (pintype "bidirectional"))
    )
    (net (code "71") (name "D4") (class "Default")
      (node (ref "CF1") (pin "3") (pinfunction "D04_3") (pintype "tri_state"))
      (node (ref "RN3") (pin "6") (pinfunction "6_6") (pintype "passive"))
      (node (ref "U12") (pin "8") (pinfunction "AD4_8") (pintype "tri_state"))
      (node (ref "U13") (pin "14") (pinfunction "B5_14") (pintype "bidirectional"))
      (node (ref "U14") (pin "14") (pinfunction "B5_14") (pintype "bidirectional"))
      (node (ref "U9") (pin "14") (pinfunction "B_14") (pintype "bidirectional"))
    )
    (net (code "72") (name "D5") (class "Default")
      (node (ref "CF1") (pin "4") (pinfunction "D05_4") (pintype "tri_state"))
      (node (ref "RN3") (pin "7") (pinfunction "7_7") (pintype "passive"))
      (node (ref "U12") (pin "9") (pinfunction "AD5_9") (pintype "tri_state"))
      (node (ref "U13") (pin "13") (pinfunction "B6_13") (pintype "bidirectional"))
      (node (ref "U14") (pin "13") (pinfunction "B6_13") (pintype "bidirectional"))
      (node (ref "U9") (pin "13") (pinfunction "B_13") (pintype "bidirectional"))
    )
    (net (code "73") (name "D6") (class "Default")
      (node (ref "CF1") (pin "5") (pinfunction "D06_5") (pintype "tri_state"))
      (node (ref "RN3") (pin "8") (pinfunction "8_8") (pintype "passive"))
      (node (ref "U12") (pin "10") (pinfunction "AD6_10") (pintype "tri_state"))
      (node (ref "U13") (pin "12") (pinfunction "B7_12") (pintype "bidirectional"))
      (node (ref "U14") (pin "12") (pinfunction "B7_12") (pintype "bidirectional"))
      (node (ref "U9") (pin "12") (pinfunction "B_12") (pintype "bidirectional"))
    )
    (net (code "74") (name "D7") (class "Default")
      (node (ref "CF1") (pin "6") (pinfunction "D07_6") (pintype "tri_state"))
      (node (ref "RN3") (pin "9") (pinfunction "9_9") (pintype "passive"))
      (node (ref "U12") (pin "11") (pinfunction "AD7_11") (pintype "tri_state"))
      (node (ref "U13") (pin "11") (pinfunction "B8_11") (pintype "bidirectional"))
      (node (ref "U14") (pin "11") (pinfunction "B8_11") (pintype "bidirectional"))
      (node (ref "U9") (pin "11") (pinfunction "B_11") (pintype "bidirectional"))
    )
    (net (code "75") (name "INT_CF") (class "Default")
      (node (ref "CF1") (pin "37") (pinfunction "INTRQ_37") (pintype "output"))
      (node (ref "U14") (pin "3") (pinfunction "A2_3") (pintype "bidirectional"))
      (node (ref "U7") (pin "1") (pinfunction "I_1") (pintype "input"))
    )
    (net (code "76") (name "INT_DISABLE") (class "Default")
      (node (ref "U11") (pin "9") (pinfunction "Q_9") (pintype "output"))
      (node (ref "U14") (pin "5") (pinfunction "A4_5") (pintype "bidirectional"))
    )
    (net (code "77") (name "Net-(CF1A-~{DASP})") (class "Default")
      (node (ref "CF1") (pin "45") (pinfunction "~{DASP}_45") (pintype "open_collector"))
      (node (ref "D1") (pin "C") (pinfunction "C_C") (pintype "passive"))
    )
    (net (code "78") (name "Net-(CF1A-~{PDIAG})") (class "Default")
      (node (ref "CF1") (pin "46") (pinfunction "~{PDIAG}_46") (pintype "output"))
      (node (ref "R11") (pin "1") (pinfunction "1_1") (pintype "passive"))
    )
    (net (code "79") (name "Net-(D1-PadA)") (class "Default")
      (node (ref "D1") (pin "A") (pinfunction "A_A") (pintype "passive"))
      (node (ref "R8") (pin "1") (pinfunction "1_1") (pintype "passive"))
    )
    (net (code "80") (name "Net-(Q1-D)") (class "Default")
      (node (ref "JP3") (pin "1") (pinfunction "1_1") (pintype "passive"))
      (node (ref "Q1") (pin "3") (pinfunction "D_3") (pintype "passive"))
    )
    (net (code "81") (name "Net-(Q1-G)") (class "Default")
      (node (ref "Q1") (pin "2") (pinfunction "G_2") (pintype "passive"))
      (node (ref "R4") (pin "2") (pinfunction "2_2") (pintype "passive"))
    )
    (net (code "82") (name "Net-(Q2-D)") (class "Default")
      (node (ref "JP4") (pin "1") (pinfunction "1_1") (pintype "passive"))
      (node (ref "Q2") (pin "3") (pinfunction "D_3") (pintype "passive"))
    )
    (net (code "83") (name "Net-(Q2-G)") (class "Default")
      (node (ref "Q2") (pin "2") (pinfunction "G_2") (pintype "passive"))
      (node (ref "R7") (pin "2") (pinfunction "2_2") (pintype "passive"))
    )
    (net (code "84") (name "Net-(RN1B-2)") (class "Default")
      (node (ref "RN1") (pin "4") (pinfunction "2_4") (pintype "passive"))
      (node (ref "U9") (pin "5") (pinfunction "A_5") (pintype "bidirectional"))
    )
    (net (code "85") (name "Net-(RN1C-2)") (class "Default")
      (node (ref "RN1") (pin "6") (pinfunction "2_6") (pintype "passive"))
      (node (ref "U9") (pin "7") (pinfunction "A_7") (pintype "bidirectional"))
    )
    (net (code "86") (name "Net-(RN1D-2)") (class "Default")
      (node (ref "RN1") (pin "8") (pinfunction "2_8") (pintype "passive"))
      (node (ref "U9") (pin "9") (pinfunction "A_9") (pintype "bidirectional"))
    )
    (net (code "87") (name "Net-(RN2B-2)") (class "Default")
      (node (ref "RN2") (pin "4") (pinfunction "2_4") (pintype "passive"))
      (node (ref "U9") (pin "4") (pinfunction "A_4") (pintype "bidirectional"))
    )
    (net (code "88") (name "Net-(RN2C-2)") (class "Default")
      (node (ref "RN2") (pin "6") (pinfunction "2_6") (pintype "passive"))
      (node (ref "U9") (pin "6") (pinfunction "A_6") (pintype "bidirectional"))
    )
    (net (code "89") (name "Net-(RN2D-2)") (class "Default")
      (node (ref "RN2") (pin "8") (pinfunction "2_8") (pintype "passive"))
      (node (ref "U9") (pin "8") (pinfunction "A_8") (pintype "bidirectional"))
    )
    (net (code "90") (name "Net-(U1B-R{slash}C)") (class "Default")
      (node (ref "C16") (pin "1") (pinfunction "1_1") (pintype "passive"))
      (node (ref "R1") (pin "1") (pinfunction "1_1") (pintype "passive"))
      (node (ref "U1") (pin "7") (pinfunction "R/C_7") (pintype "input"))
    )
    (net (code "91") (name "Net-(U5A-Y4)") (class "Default")
      (node (ref "U5") (pin "11") (pinfunction "Y4_11") (pintype "output"))
      (node (ref "U7") (pin "11") (pinfunction "I_11") (pintype "input"))
    )
    (net (code "92") (name "Net-(U7A-O)") (class "Default")
      (node (ref "R7") (pin "1") (pinfunction "1_1") (pintype "passive"))
      (node (ref "U7") (pin "12") (pinfunction "O_12") (pintype "output"))
    )
    (net (code "93") (name "Net-(U7C-I)") (class "Default")
      (node (ref "U7") (pin "6") (pinfunction "O_6") (pintype "output"))
      (node (ref "U7") (pin "9") (pinfunction "I_9") (pintype "input"))
    )
    (net (code "94") (name "Net-(U7D-O)") (class "Default")
      (node (ref "JP2") (pin "1") (pinfunction "1_1") (pintype "passive"))
      (node (ref "U7") (pin "2") (pinfunction "O_2") (pintype "output"))
    )
    (net (code "95") (name "Net-(U9A-A)") (class "Default")
      (node (ref "RN2") (pin "2") (pinfunction "2_2") (pintype "passive"))
      (node (ref "U9") (pin "2") (pinfunction "A_2") (pintype "bidirectional"))
    )
    (net (code "96") (name "Net-(U9B-A)") (class "Default")
      (node (ref "RN1") (pin "2") (pinfunction "2_2") (pintype "passive"))
      (node (ref "U9") (pin "3") (pinfunction "A_3") (pintype "bidirectional"))
    )
    (net (code "97") (name "Net-(U10A-I0)") (class "Default")
      (node (ref "JP6") (pin "2") (pinfunction "2_2") (pintype "passive"))
      (node (ref "R6") (pin "1") (pinfunction "1_1") (pintype "passive"))
      (node (ref "U10") (pin "1") (pinfunction "I0_1") (pintype "input"))
    )
    (net (code "98") (name "Net-(U10A-I1)") (class "Default")
      (node (ref "JP1") (pin "2") (pinfunction "2_2") (pintype "passive"))
      (node (ref "R2") (pin "1") (pinfunction "1_1") (pintype "passive"))
      (node (ref "U10") (pin "2") (pinfunction "I1_2") (pintype "input"))
    )
    (net (code "99") (name "Net-(U10A-O)") (class "Default")
      (node (ref "R4") (pin "1") (pinfunction "1_1") (pintype "passive"))
      (node (ref "U10") (pin "3") (pinfunction "O_3") (pintype "output"))
    )
    (net (code "100") (name "Net-(U10C-I0)") (class "Default")
      (node (ref "U10") (pin "11") (pinfunction "O_11") (pintype "output"))
      (node (ref "U10") (pin "9") (pinfunction "I0_9") (pintype "input"))
    )
    (net (code "101") (name "Net-(U10C-I1)") (class "Default")
      (node (ref "U10") (pin "10") (pinfunction "I1_10") (pintype "input"))
      (node (ref "U11") (pin "8") (pinfunction "~{Q}_8") (pintype "output"))
    )
    (net (code "102") (name "Net-(U10C-O)") (class "Default")
      (node (ref "U10") (pin "8") (pinfunction "O_8") (pintype "output"))
      (node (ref "U7") (pin "13") (pinfunction "I_13") (pintype "input"))
    )
    (net (code "103") (name "Net-(U10D-I0)") (class "Default")
      (node (ref "JP2") (pin "2") (pinfunction "2_2") (pintype "passive"))
      (node (ref "R5") (pin "1") (pinfunction "1_1") (pintype "passive"))
      (node (ref "U10") (pin "12") (pinfunction "I0_12") (pintype "input"))
    )
    (net (code "104") (name "Net-(U12-+5V)") (class "Default")
      (node (ref "C12") (pin "1") (pinfunction "1_1") (pintype "passive"))
      (node (ref "U12") (pin "24") (pinfunction "+5V_24") (pintype "input"))
      (node (ref "U15") (pin "1") (pinfunction "VO_1") (pintype "passive"))
    )
    (net (code "105") (name "Net-(U12-ALE)") (class "Default")
      (node (ref "U12") (pin "14") (pinfunction "ALE_14") (pintype "tri_state"))
      (node (ref "U7") (pin "10") (pinfunction "O_10") (pintype "output"))
    )
    (net (code "106") (name "Net-(U12-SQW)") (class "Default")
      (node (ref "TP1") (pin "1") (pinfunction "1_1") (pintype "passive"))
      (node (ref "U12") (pin "23") (pinfunction "SQW_23") (pintype "output"))
    )
    (net (code "107") (name "Net-(U12-VBAUX)") (class "Default")
      (node (ref "BT1") (pin "P1") (pinfunction "+_P1") (pintype "passive"))
      (node (ref "BT1") (pin "P2") (pinfunction "+_P2") (pintype "passive"))
      (node (ref "R9") (pin "2") (pinfunction "2_2") (pintype "passive"))
      (node (ref "U12") (pin "22") (pinfunction "VBAUX_22") (pintype "input"))
    )
    (net (code "108") (name "Net-(U12-X1)") (class "Default")
      (node (ref "U12") (pin "2") (pinfunction "X1_2") (pintype "input"))
      (node (ref "Y1") (pin "2") (pinfunction "2_2") (pintype "passive"))
    )
    (net (code "109") (name "Net-(U12-X2)") (class "Default")
      (node (ref "U12") (pin "3") (pinfunction "X2_3") (pintype "input"))
      (node (ref "Y1") (pin "1") (pinfunction "1_1") (pintype "passive"))
    )
    (net (code "110") (name "Net-(U12-~{KS})") (class "Default")
      (node (ref "J2") (pin "1") (pinfunction "1_1") (pintype "passive"))
      (node (ref "R9") (pin "1") (pinfunction "1_1") (pintype "passive"))
      (node (ref "U12") (pin "18") (pinfunction "~{KS}_18") (pintype "tri_state"))
    )
    (net (code "111") (name "Net-(U12-~{PWR})") (class "Default")
      (node (ref "J1") (pin "1") (pinfunction "1_1") (pintype "passive"))
      (node (ref "U12") (pin "1") (pinfunction "~{PWR}_1") (pintype "open_collector"))
    )
    (net (code "112") (name "Net-(U12-~{RCLR})") (class "Default")
      (node (ref "JP5") (pin "1") (pinfunction "1_1") (pintype "passive"))
      (node (ref "U12") (pin "21") (pinfunction "~{RCLR}_21") (pintype "tri_state"))
    )
    (net (code "113") (name "Net-(U12-~{RD})") (class "Default")
      (node (ref "U12") (pin "17") (pinfunction "~{RD}_17") (pintype "tri_state"))
      (node (ref "U5") (pin "12") (pinfunction "Y3_12") (pintype "output"))
    )
    (net (code "114") (name "Net-(U12-~{WR})") (class "Default")
      (node (ref "U12") (pin "15") (pinfunction "~{WR}_15") (pintype "tri_state"))
      (node (ref "U5") (pin "10") (pinfunction "Y5_10") (pintype "output"))
    )
    (net (code "115") (name "Net-(U15-VI)") (class "Default")
      (node (ref "C19") (pin "1") (pinfunction "1_1") (pintype "passive"))
      (node (ref "D2") (pin "C") (pinfunction "C_C") (pintype "passive"))
      (node (ref "U15") (pin "3") (pinfunction "VI_3") (pintype "input"))
    )
    (net (code "116") (name "RWCYCLE") (class "Default")
      (node (ref "TP6") (pin "1") (pinfunction "1_1") (pintype "passive"))
      (node (ref "U1") (pin "10") (pinfunction "B_10") (pintype "input"))
      (node (ref "U10") (pin "6") (pinfunction "O_6") (pintype "output"))
    )
    (net (code "117") (name "SR_RTC") (class "Default")
      (node (ref "U14") (pin "2") (pinfunction "A1_2") (pintype "bidirectional"))
      (node (ref "U7") (pin "4") (pinfunction "O_4") (pintype "output"))
    )
    (net (code "118") (name "unconnected-(CF1A-D08-Pad47)") (class "Default")
      (node (ref "CF1") (pin "47") (pinfunction "D08_47") (pintype "tri_state"))
    )
    (net (code "119") (name "unconnected-(CF1A-D09-Pad48)") (class "Default")
      (node (ref "CF1") (pin "48") (pinfunction "D09_48") (pintype "tri_state"))
    )
    (net (code "120") (name "unconnected-(CF1A-D10-Pad49)") (class "Default")
      (node (ref "CF1") (pin "49") (pinfunction "D10_49") (pintype "tri_state"))
    )
    (net (code "121") (name "unconnected-(CF1A-D11-Pad27)") (class "Default")
      (node (ref "CF1") (pin "27") (pinfunction "D11_27") (pintype "tri_state"))
    )
    (net (code "122") (name "unconnected-(CF1A-D12-Pad28)") (class "Default")
      (node (ref "CF1") (pin "28") (pinfunction "D12_28") (pintype "tri_state"))
    )
    (net (code "123") (name "unconnected-(CF1A-D13-Pad29)") (class "Default")
      (node (ref "CF1") (pin "29") (pinfunction "D13_29") (pintype "tri_state"))
    )
    (net (code "124") (name "unconnected-(CF1A-D14-Pad30)") (class "Default")
      (node (ref "CF1") (pin "30") (pinfunction "D14_30") (pintype "tri_state"))
    )
    (net (code "125") (name "unconnected-(CF1A-D15-Pad31)") (class "Default")
      (node (ref "CF1") (pin "31") (pinfunction "D15_31") (pintype "tri_state"))
    )
    (net (code "126") (name "unconnected-(CF1A-DMARQ-Pad43)") (class "Default")
      (node (ref "CF1") (pin "43") (pinfunction "DMARQ_43") (pintype "output"))
    )
    (net (code "127") (name "unconnected-(CF1A-~{CD2}-Pad25)") (class "Default")
      (node (ref "CF1") (pin "25") (pinfunction "~{CD2}_25") (pintype "output"))
    )
    (net (code "128") (name "unconnected-(CF1A-~{IOCS16}-Pad24)") (class "Default")
      (node (ref "CF1") (pin "24") (pinfunction "~{IOCS16}_24") (pintype "output"))
    )
    (net (code "129") (name "unconnected-(CF1A-~{VS1}-Pad33)") (class "Default")
      (node (ref "CF1") (pin "33") (pinfunction "~{VS1}_33") (pintype "output"))
    )
    (net (code "130") (name "unconnected-(CF1A-~{VS2}-Pad40)") (class "Default")
      (node (ref "CF1") (pin "40") (pinfunction "~{VS2}_40") (pintype "output"))
    )
    (net (code "131") (name "unconnected-(P1-+3.3V-Pad2)") (class "Default")
      (node (ref "P1") (pin "2") (pinfunction "+3.3V_2") (pintype "bidirectional"))
    )
    (net (code "132") (name "unconnected-(P1-+5VSB-Pad8)") (class "Default")
      (node (ref "P1") (pin "8") (pinfunction "+5VSB_8") (pintype "bidirectional"))
    )
    (net (code "133") (name "unconnected-(P1--12V-Pad7)") (class "Default")
      (node (ref "P1") (pin "7") (pinfunction "-12V_7") (pintype "bidirectional"))
    )
    (net (code "134") (name "unconnected-(P1-A3-Pad25)") (class "Default")
      (node (ref "P1") (pin "25") (pinfunction "A3_25") (pintype "bidirectional"))
    )
    (net (code "135") (name "unconnected-(P1-A8-Pad30)") (class "Default")
      (node (ref "P1") (pin "30") (pinfunction "A8_30") (pintype "bidirectional"))
    )
    (net (code "136") (name "unconnected-(P1-A9-Pad31)") (class "Default")
      (node (ref "P1") (pin "31") (pinfunction "A9_31") (pintype "bidirectional"))
    )
    (net (code "137") (name "unconnected-(P1-A10-Pad32)") (class "Default")
      (node (ref "P1") (pin "32") (pinfunction "A10_32") (pintype "bidirectional"))
    )
    (net (code "138") (name "unconnected-(P1-A11-Pad33)") (class "Default")
      (node (ref "P1") (pin "33") (pinfunction "A11_33") (pintype "bidirectional"))
    )
    (net (code "139") (name "unconnected-(P1-A12-Pad34)") (class "Default")
      (node (ref "P1") (pin "34") (pinfunction "A12_34") (pintype "bidirectional"))
    )
    (net (code "140") (name "unconnected-(P1-A13-Pad35)") (class "Default")
      (node (ref "P1") (pin "35") (pinfunction "A13_35") (pintype "bidirectional"))
    )
    (net (code "141") (name "unconnected-(P1-A14-Pad36)") (class "Default")
      (node (ref "P1") (pin "36") (pinfunction "A14_36") (pintype "bidirectional"))
    )
    (net (code "142") (name "unconnected-(P1-A15-Pad37)") (class "Default")
      (node (ref "P1") (pin "37") (pinfunction "A15_37") (pintype "bidirectional"))
    )
    (net (code "143") (name "unconnected-(P1-A16-Pad38)") (class "Default")
      (node (ref "P1") (pin "38") (pinfunction "A16_38") (pintype "bidirectional"))
    )
    (net (code "144") (name "unconnected-(P1-A17-Pad39)") (class "Default")
      (node (ref "P1") (pin "39") (pinfunction "A17_39") (pintype "bidirectional"))
    )
    (net (code "145") (name "unconnected-(P1-A18-Pad40)") (class "Default")
      (node (ref "P1") (pin "40") (pinfunction "A18_40") (pintype "bidirectional"))
    )
    (net (code "146") (name "unconnected-(P1-A19-Pad41)") (class "Default")
      (node (ref "P1") (pin "41") (pinfunction "A19_41") (pintype "bidirectional"))
    )
    (net (code "147") (name "unconnected-(P1-CLK-Pad13)") (class "Default")
      (node (ref "P1") (pin "13") (pinfunction "CLK_13") (pintype "bidirectional"))
    )
    (net (code "148") (name "unconnected-(P1-~{BUSAK}-Pad12)") (class "Default")
      (node (ref "P1") (pin "12") (pinfunction "~{BUSAK}_12") (pintype "bidirectional"))
    )
    (net (code "149") (name "unconnected-(P1-~{BUSRQ}-Pad11)") (class "Default")
      (node (ref "P1") (pin "11") (pinfunction "~{BUSRQ}_11") (pintype "bidirectional"))
    )
    (net (code "150") (name "unconnected-(P1-~{FETCH}-Pad14)") (class "Default")
      (node (ref "P1") (pin "14") (pinfunction "~{FETCH}_14") (pintype "bidirectional"))
    )
    (net (code "151") (name "unconnected-(P1-~{HALT}-Pad15)") (class "Default")
      (node (ref "P1") (pin "15") (pinfunction "~{HALT}_15") (pintype "bidirectional"))
    )
    (net (code "152") (name "unconnected-(P1-~{INH}-Pad17)") (class "Default")
      (node (ref "P1") (pin "17") (pinfunction "~{INH}_17") (pintype "bidirectional"))
    )
    (net (code "153") (name "unconnected-(P1-~{IOSEL}-Pad18)") (class "Default")
      (node (ref "P1") (pin "18") (pinfunction "~{IOSEL}_18") (pintype "bidirectional"))
    )
    (net (code "154") (name "unconnected-(P1-~{NMI}-Pad61)") (class "Default")
      (node (ref "P1") (pin "61") (pinfunction "~{NMI}_61") (pintype "bidirectional"))
    )
    (net (code "155") (name "unconnected-(P1-~{SINT}-Pad51)") (class "Default")
      (node (ref "P1") (pin "51") (pinfunction "~{SINT}_51") (pintype "bidirectional"))
    )
    (net (code "156") (name "unconnected-(P1-~{V0}-Pad53)") (class "Default")
      (node (ref "P1") (pin "53") (pinfunction "~{V0}_53") (pintype "bidirectional"))
    )
    (net (code "157") (name "unconnected-(P1-~{V1}-Pad54)") (class "Default")
      (node (ref "P1") (pin "54") (pinfunction "~{V1}_54") (pintype "bidirectional"))
    )
    (net (code "158") (name "unconnected-(P1-~{V2}-Pad55)") (class "Default")
      (node (ref "P1") (pin "55") (pinfunction "~{V2}_55") (pintype "bidirectional"))
    )
    (net (code "159") (name "unconnected-(P1-~{V3}-Pad56)") (class "Default")
      (node (ref "P1") (pin "56") (pinfunction "~{V3}_56") (pintype "bidirectional"))
    )
    (net (code "160") (name "unconnected-(P1-~{V4}-Pad57)") (class "Default")
      (node (ref "P1") (pin "57") (pinfunction "~{V4}_57") (pintype "bidirectional"))
    )
    (net (code "161") (name "unconnected-(P1-~{V5}-Pad58)") (class "Default")
      (node (ref "P1") (pin "58") (pinfunction "~{V5}_58") (pintype "bidirectional"))
    )
    (net (code "162") (name "unconnected-(P1-~{V6}-Pad59)") (class "Default")
      (node (ref "P1") (pin "59") (pinfunction "~{V6}_59") (pintype "bidirectional"))
    )
    (net (code "163") (name "unconnected-(P1-~{V7}-Pad60)") (class "Default")
      (node (ref "P1") (pin "60") (pinfunction "~{V7}_60") (pintype "bidirectional"))
    )
    (net (code "164") (name "unconnected-(U1A-C-Pad14)") (class "Default")
      (node (ref "U1") (pin "14") (pinfunction "C_14") (pintype "input"))
    )
    (net (code "165") (name "unconnected-(U1A-Q-Pad13)") (class "Default")
      (node (ref "U1") (pin "13") (pinfunction "Q_13") (pintype "output"))
    )
    (net (code "166") (name "unconnected-(U1A-R{slash}C-Pad15)") (class "Default")
      (node (ref "U1") (pin "15") (pinfunction "R/C_15") (pintype "input"))
    )
    (net (code "167") (name "unconnected-(U1A-~{Q}-Pad4)") (class "Default")
      (node (ref "U1") (pin "4") (pinfunction "~{Q}_4") (pintype "output"))
    )
    (net (code "168") (name "unconnected-(U1B-Q-Pad5)") (class "Default")
      (node (ref "U1") (pin "5") (pinfunction "Q_5") (pintype "output"))
    )
    (net (code "169") (name "unconnected-(U2A-Y3-Pad12)") (class "Default")
      (node (ref "U2") (pin "12") (pinfunction "Y3_12") (pintype "output"))
    )
    (net (code "170") (name "unconnected-(U2A-Y4-Pad11)") (class "Default")
      (node (ref "U2") (pin "11") (pinfunction "Y4_11") (pintype "output"))
    )
    (net (code "171") (name "unconnected-(U2A-Y5-Pad10)") (class "Default")
      (node (ref "U2") (pin "10") (pinfunction "Y5_10") (pintype "output"))
    )
    (net (code "172") (name "unconnected-(U2A-Y6-Pad9)") (class "Default")
      (node (ref "U2") (pin "9") (pinfunction "Y6_9") (pintype "output"))
    )
    (net (code "173") (name "unconnected-(U2A-Y7-Pad7)") (class "Default")
      (node (ref "U2") (pin "7") (pinfunction "Y7_7") (pintype "output"))
    )
    (net (code "174") (name "unconnected-(U3A-Y1-Pad14)") (class "Default")
      (node (ref "U3") (pin "14") (pinfunction "Y1_14") (pintype "output"))
    )
    (net (code "175") (name "unconnected-(U3A-Y2-Pad13)") (class "Default")
      (node (ref "U3") (pin "13") (pinfunction "Y2_13") (pintype "output"))
    )
    (net (code "176") (name "unconnected-(U3A-Y3-Pad12)") (class "Default")
      (node (ref "U3") (pin "12") (pinfunction "Y3_12") (pintype "output"))
    )
    (net (code "177") (name "unconnected-(U3A-Y4-Pad11)") (class "Default")
      (node (ref "U3") (pin "11") (pinfunction "Y4_11") (pintype "output"))
    )
    (net (code "178") (name "unconnected-(U3A-Y5-Pad10)") (class "Default")
      (node (ref "U3") (pin "10") (pinfunction "Y5_10") (pintype "output"))
    )
    (net (code "179") (name "unconnected-(U3A-Y6-Pad9)") (class "Default")
      (node (ref "U3") (pin "9") (pinfunction "Y6_9") (pintype "output"))
    )
    (net (code "180") (name "unconnected-(U3A-Y7-Pad7)") (class "Default")
      (node (ref "U3") (pin "7") (pinfunction "Y7_7") (pintype "output"))
    )
    (net (code "181") (name "unconnected-(U4A-Y1-Pad14)") (class "Default")
      (node (ref "U4") (pin "14") (pinfunction "Y1_14") (pintype "output"))
    )
    (net (code "182") (name "unconnected-(U4A-Y2-Pad13)") (class "Default")
      (node (ref "U4") (pin "13") (pinfunction "Y2_13") (pintype "output"))
    )
    (net (code "183") (name "unconnected-(U4A-Y3-Pad12)") (class "Default")
      (node (ref "U4") (pin "12") (pinfunction "Y3_12") (pintype "output"))
    )
    (net (code "184") (name "unconnected-(U4A-Y4-Pad11)") (class "Default")
      (node (ref "U4") (pin "11") (pinfunction "Y4_11") (pintype "output"))
    )
    (net (code "185") (name "unconnected-(U4A-Y5-Pad10)") (class "Default")
      (node (ref "U4") (pin "10") (pinfunction "Y5_10") (pintype "output"))
    )
    (net (code "186") (name "unconnected-(U4A-Y6-Pad9)") (class "Default")
      (node (ref "U4") (pin "9") (pinfunction "Y6_9") (pintype "output"))
    )
    (net (code "187") (name "unconnected-(U5A-Y0-Pad15)") (class "Default")
      (node (ref "U5") (pin "15") (pinfunction "Y0_15") (pintype "output"))
    )
    (net (code "188") (name "unconnected-(U5A-Y1-Pad14)") (class "Default")
      (node (ref "U5") (pin "14") (pinfunction "Y1_14") (pintype "output"))
    )
    (net (code "189") (name "unconnected-(U5A-Y2-Pad13)") (class "Default")
      (node (ref "U5") (pin "13") (pinfunction "Y2_13") (pintype "output"))
    )
    (net (code "190") (name "unconnected-(U5A-Y6-Pad9)") (class "Default")
      (node (ref "U5") (pin "9") (pinfunction "Y6_9") (pintype "output"))
    )
    (net (code "191") (name "unconnected-(U5A-Y7-Pad7)") (class "Default")
      (node (ref "U5") (pin "7") (pinfunction "Y7_7") (pintype "output"))
    )
    (net (code "192") (name "unconnected-(U6A-B-Pad18)") (class "Default")
      (node (ref "U6") (pin "18") (pinfunction "B_18") (pintype "bidirectional"))
    )
    (net (code "193") (name "unconnected-(U6B-B-Pad17)") (class "Default")
      (node (ref "U6") (pin "17") (pinfunction "B_17") (pintype "bidirectional"))
    )
    (net (code "194") (name "unconnected-(U6G-B-Pad12)") (class "Default")
      (node (ref "U6") (pin "12") (pinfunction "B_12") (pintype "bidirectional"))
    )
    (net (code "195") (name "unconnected-(U6H-B-Pad11)") (class "Default")
      (node (ref "U6") (pin "11") (pinfunction "B_11") (pintype "bidirectional"))
    )
    (net (code "196") (name "unconnected-(U8G-B-Pad12)") (class "Default")
      (node (ref "U8") (pin "12") (pinfunction "B_12") (pintype "bidirectional"))
    )
    (net (code "197") (name "unconnected-(U8H-B-Pad11)") (class "Default")
      (node (ref "U8") (pin "11") (pinfunction "B_11") (pintype "bidirectional"))
    )
    (net (code "198") (name "unconnected-(U11A-Q-Pad5)") (class "Default")
      (node (ref "U11") (pin "5") (pinfunction "Q_5") (pintype "output"))
    )
    (net (code "199") (name "unconnected-(U11A-~{Q}-Pad6)") (class "Default")
      (node (ref "U11") (pin "6") (pinfunction "~{Q}_6") (pintype "output"))
    )
    (net (code "200") (name "~{BCSX}") (class "Default")
      (node (ref "P1") (pin "9") (pinfunction "~{CSX}_9") (pintype "bidirectional"))
      (node (ref "U8") (pin "2") (pinfunction "A_2") (pintype "bidirectional"))
    )
    (net (code "201") (name "~{BIRQX}") (class "Default")
      (node (ref "JP4") (pin "2") (pinfunction "2_2") (pintype "passive"))
      (node (ref "P1") (pin "52") (pinfunction "~{IRQX}_52") (pintype "bidirectional"))
    )
    (net (code "202") (name "~{BRD}") (class "Default")
      (node (ref "P1") (pin "19") (pinfunction "~{RD}_19") (pintype "bidirectional"))
      (node (ref "U10") (pin "4") (pinfunction "I0_4") (pintype "input"))
      (node (ref "U8") (pin "3") (pinfunction "A_3") (pintype "bidirectional"))
    )
    (net (code "203") (name "~{BRST}") (class "Default")
      (node (ref "P1") (pin "10") (pinfunction "~{RST}_10") (pintype "bidirectional"))
      (node (ref "U7") (pin "5") (pinfunction "I_5") (pintype "input"))
    )
    (net (code "204") (name "~{BWAIT}") (class "Default")
      (node (ref "JP3") (pin "2") (pinfunction "2_2") (pintype "passive"))
      (node (ref "P1") (pin "16") (pinfunction "~{WAIT}_16") (pintype "bidirectional"))
    )
    (net (code "205") (name "~{BWR}") (class "Default")
      (node (ref "P1") (pin "20") (pinfunction "~{WR}_20") (pintype "bidirectional"))
      (node (ref "U10") (pin "5") (pinfunction "I1_5") (pintype "input"))
      (node (ref "U8") (pin "4") (pinfunction "A_4") (pintype "bidirectional"))
    )
    (net (code "206") (name "~{CF_CD}") (class "Default")
      (node (ref "CF1") (pin "26") (pinfunction "~{CD1}_26") (pintype "output"))
      (node (ref "R10") (pin "2") (pinfunction "2_2") (pintype "passive"))
      (node (ref "U14") (pin "4") (pinfunction "A3_4") (pintype "bidirectional"))
    )
    (net (code "207") (name "~{CSX}") (class "Default")
      (node (ref "TP4") (pin "1") (pinfunction "1_1") (pintype "passive"))
      (node (ref "U1") (pin "9") (pinfunction "A_9") (pintype "input"))
      (node (ref "U2") (pin "4") (pinfunction "G2A_4") (pintype "input"))
      (node (ref "U3") (pin "4") (pinfunction "G2A_4") (pintype "input"))
      (node (ref "U4") (pin "4") (pinfunction "G2A_4") (pintype "input"))
      (node (ref "U8") (pin "18") (pinfunction "B_18") (pintype "bidirectional"))
      (node (ref "U9") (pin "19") (pinfunction "~{OE}_19") (pintype "input"))
    )
    (net (code "208") (name "~{CS_CF0}") (class "Default")
      (node (ref "CF1") (pin "7") (pinfunction "~{CS0}_7") (pintype "input"))
      (node (ref "U2") (pin "15") (pinfunction "Y0_15") (pintype "output"))
    )
    (net (code "209") (name "~{CS_CF1}") (class "Default")
      (node (ref "CF1") (pin "32") (pinfunction "~{CS1}_32") (pintype "input"))
      (node (ref "U2") (pin "14") (pinfunction "Y1_14") (pintype "output"))
    )
    (net (code "210") (name "~{CS_ID}") (class "Default")
      (node (ref "U13") (pin "19") (pinfunction "~{OE}_19") (pintype "input"))
      (node (ref "U4") (pin "7") (pinfunction "Y7_7") (pintype "output"))
    )
    (net (code "211") (name "~{CS_IER}") (class "Default")
      (node (ref "U11") (pin "11") (pinfunction "CLK_11") (pintype "input"))
      (node (ref "U3") (pin "15") (pinfunction "Y0_15") (pintype "output"))
    )
    (net (code "212") (name "~{CS_RTC}") (class "Default")
      (node (ref "U12") (pin "13") (pinfunction "~{CS}_13") (pintype "tri_state"))
      (node (ref "U2") (pin "13") (pinfunction "Y2_13") (pintype "output"))
      (node (ref "U5") (pin "4") (pinfunction "G2A_4") (pintype "input"))
    )
    (net (code "213") (name "~{CS_SR}") (class "Default")
      (node (ref "U14") (pin "19") (pinfunction "~{OE}_19") (pintype "input"))
      (node (ref "U4") (pin "15") (pinfunction "Y0_15") (pintype "output"))
    )
    (net (code "214") (name "~{INT_RTC}") (class "Default")
      (node (ref "R3") (pin "2") (pinfunction "2_2") (pintype "passive"))
      (node (ref "U10") (pin "13") (pinfunction "I1_13") (pintype "input"))
      (node (ref "U12") (pin "19") (pinfunction "~{IRQ}_19") (pintype "open_collector"))
      (node (ref "U7") (pin "3") (pinfunction "I_3") (pintype "input"))
    )
    (net (code "215") (name "~{RD}") (class "Default")
      (node (ref "CF1") (pin "34") (pinfunction "~{IORD}_34") (pintype "input"))
      (node (ref "U4") (pin "5") (pinfunction "G2B_5") (pintype "input"))
      (node (ref "U5") (pin "3") (pinfunction "C_3") (pintype "input"))
      (node (ref "U8") (pin "17") (pinfunction "B_17") (pintype "bidirectional"))
      (node (ref "U9") (pin "1") (pinfunction "DIR_1") (pintype "input"))
    )
    (net (code "216") (name "~{RST}") (class "Default")
      (node (ref "CF1") (pin "41") (pinfunction "/RESET_41") (pintype "input"))
      (node (ref "U1") (pin "11") (pinfunction "CLR_11") (pintype "input"))
      (node (ref "U11") (pin "10") (pinfunction "PRE_10") (pintype "input"))
      (node (ref "U7") (pin "8") (pinfunction "O_8") (pintype "output"))
    )
    (net (code "217") (name "~{WAIT_CF}") (class "Default")
      (node (ref "CF1") (pin "42") (pinfunction "IORDY_42") (pintype "output"))
      (node (ref "JP6") (pin "1") (pinfunction "1_1") (pintype "passive"))
    )
    (net (code "218") (name "~{WAIT_CSX}") (class "Default")
      (node (ref "JP1") (pin "1") (pinfunction "1_1") (pintype "passive"))
      (node (ref "TP5") (pin "1") (pinfunction "1_1") (pintype "passive"))
      (node (ref "U1") (pin "12") (pinfunction "~{Q}_12") (pintype "output"))
    )
    (net (code "219") (name "~{WR}") (class "Default")
      (node (ref "CF1") (pin "35") (pinfunction "~{IOWR}_35") (pintype "input"))
      (node (ref "U3") (pin "5") (pinfunction "G2B_5") (pintype "input"))
      (node (ref "U5") (pin "2") (pinfunction "B_2") (pintype "input"))
      (node (ref "U8") (pin "16") (pinfunction "B_16") (pintype "bidirectional"))
    )
  )
)
